# betaV2_2.net
KiCad netlist of a schematic drawn in Altium Designer
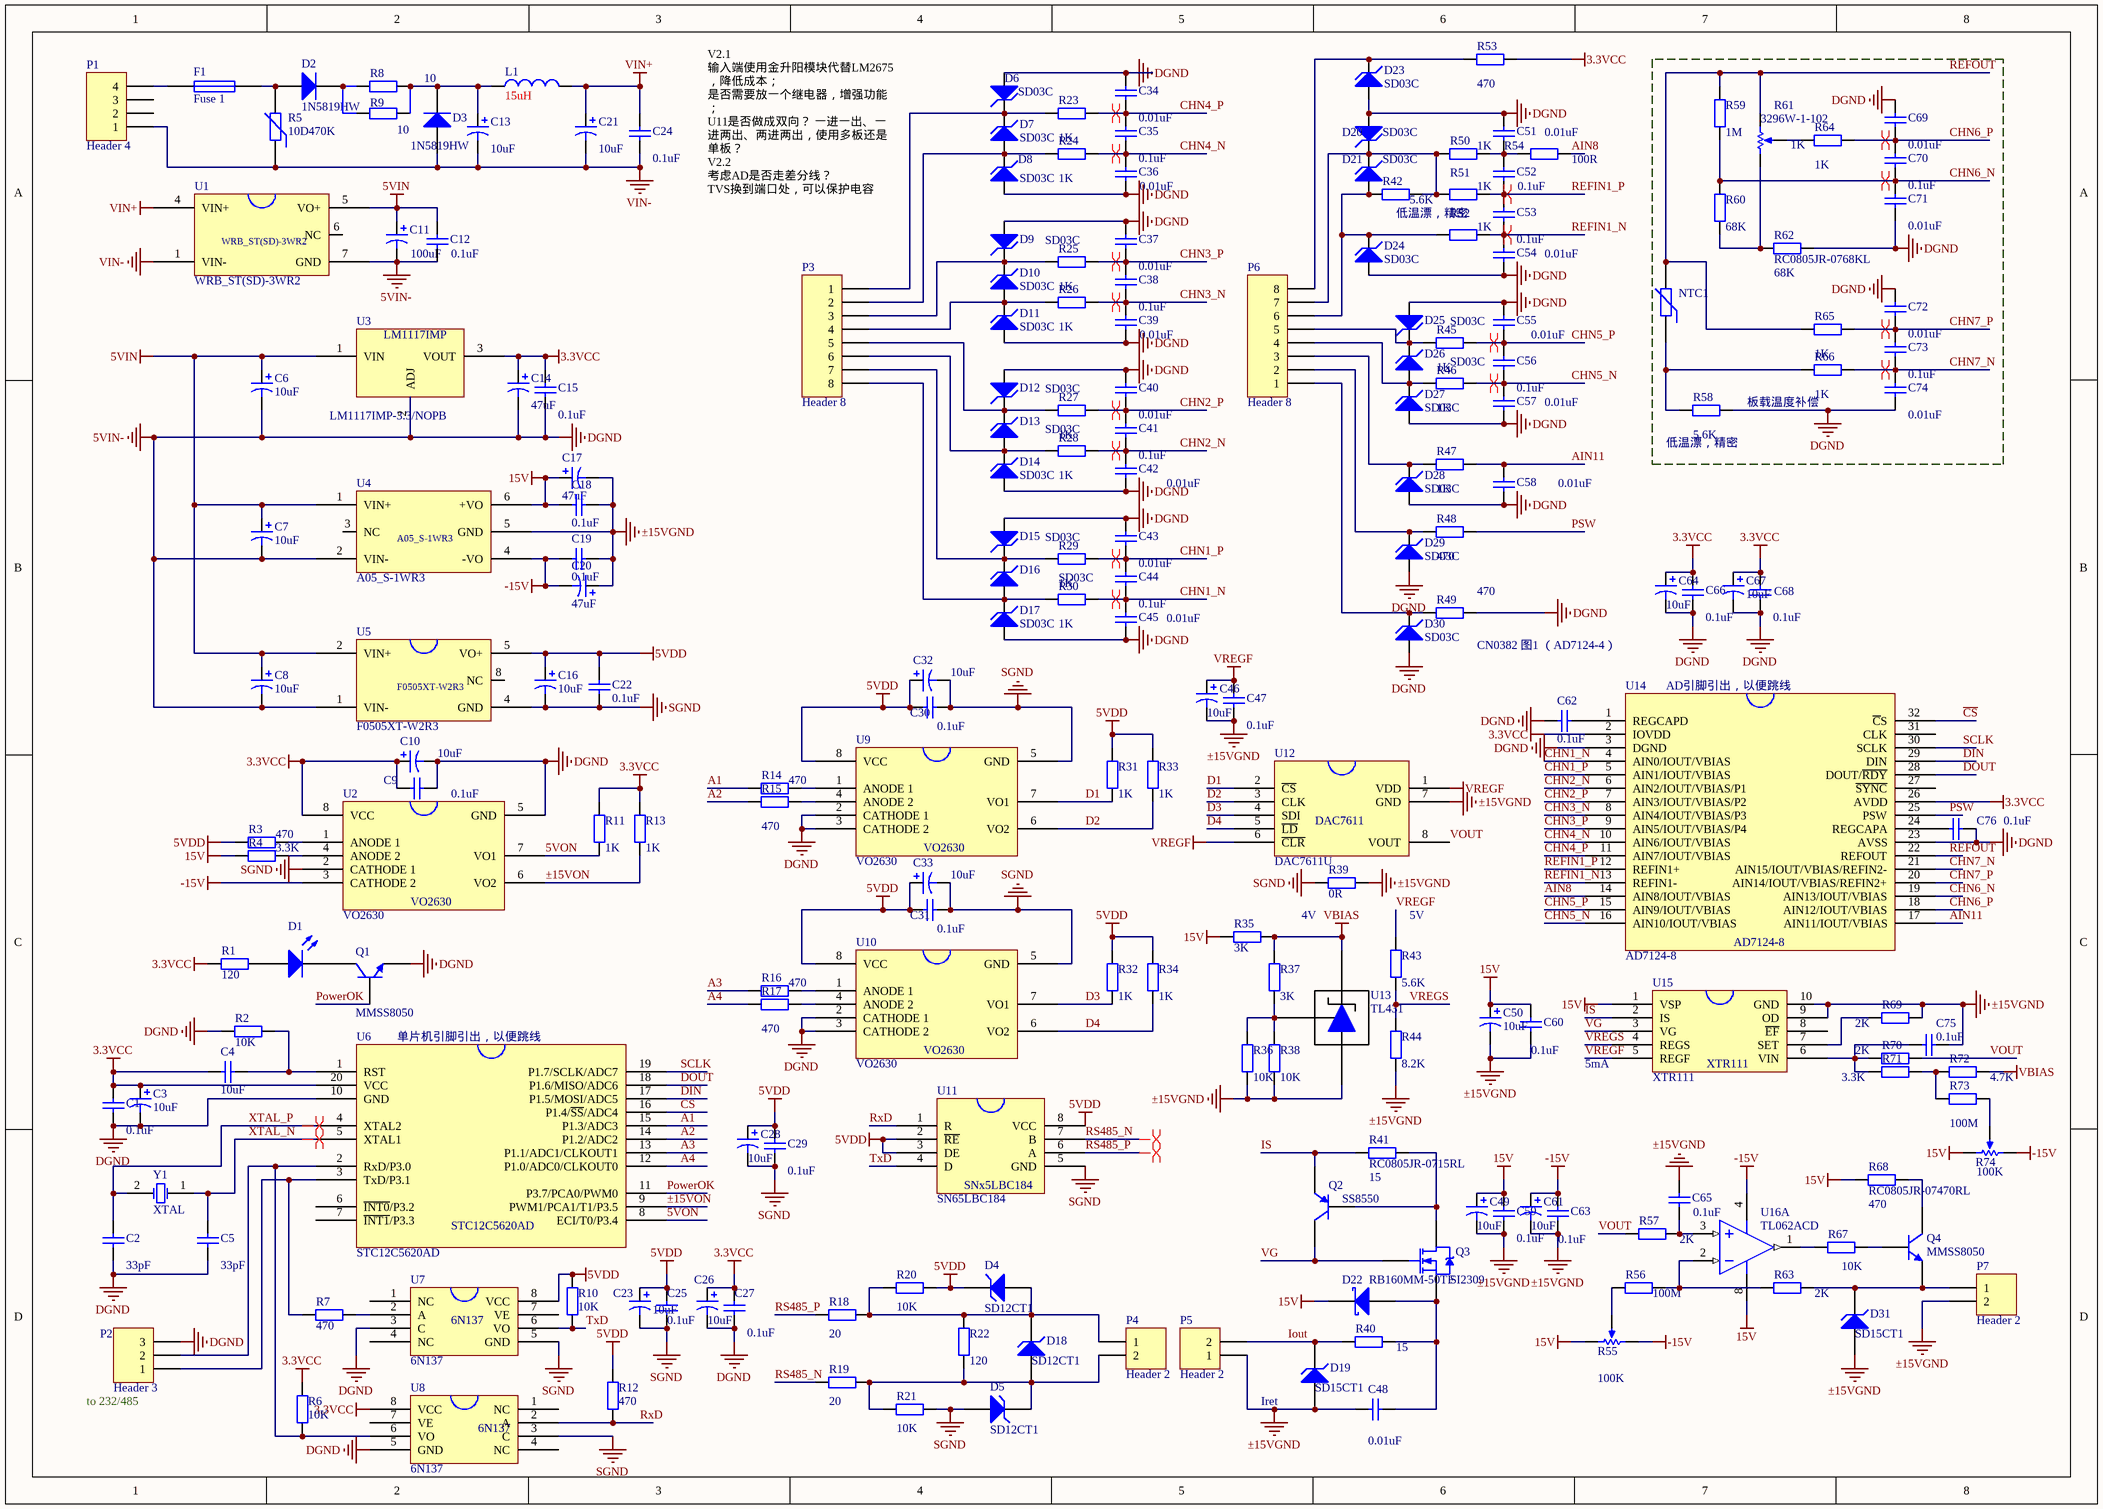
[diagram p0: betaV2.2.SchDoc]

(export (version "E")
  (design (tool "Eeschema 10.0.6"))
  (components
    (comp (ref "C1")
      (value "0.1uF")
      (footprint "0805c")
      (description "Capacitor")
      (fields (field (name "Comment") "CC0805MRX7R9BB104"))
      (libsource (lib "Miscellaneous Devices") (part "Cap"))
    )
    (comp (ref "C2")
      (value "33pF")
      (footprint "0805c")
      (description "Capacitor")
      (fields (field (name "Comment") "CC0805MRX7R9BB330") (field (name "PUBLISHER") "Altium Limited"))
      (libsource (lib "Miscellaneous Devices") (part "Cap"))
    )
    (comp (ref "C3")
      (value "10uF")
      (footprint "CB")
      (description "Polarized Capacitor (Radial)")
      (fields (field (name "Comment") "T494B106M006AHAUTO") (field (name "PUBLISHER") "Altium Limited"))
      (libsource (lib "Miscellaneous Devices") (part "Cap Pol1"))
    )
    (comp (ref "C4")
      (value "10uF")
      (footprint "0805c")
      (description "Capacitor")
      (fields (field (name "Comment") "CC0805MRX7R9BB106"))
      (libsource (lib "Miscellaneous Devices") (part "Cap"))
    )
    (comp (ref "C5")
      (value "33pF")
      (footprint "0805c")
      (description "Capacitor")
      (fields (field (name "Comment") "CC0805MRX7R9BB330") (field (name "PUBLISHER") "Altium Limited"))
      (libsource (lib "Miscellaneous Devices") (part "Cap"))
    )
    (comp (ref "C6")
      (value "10uF")
      (footprint "CB")
      (description "Polarized Capacitor (Radial)")
      (fields (field (name "Comment") "T494B106M006AHAUTO") (field (name "PUBLISHER") "Altium Limited"))
      (libsource (lib "Miscellaneous Devices") (part "Cap Pol1"))
    )
    (comp (ref "C7")
      (value "10uF")
      (footprint "CB")
      (description "Polarized Capacitor (Radial)")
      (fields (field (name "Comment") "T494B106M006AHAUTO") (field (name "PUBLISHER") "Altium Limited"))
      (libsource (lib "Miscellaneous Devices") (part "Cap Pol1"))
    )
    (comp (ref "C8")
      (value "10uF")
      (footprint "CB")
      (description "Polarized Capacitor (Radial)")
      (fields (field (name "Comment") "T494B106M006AHAUTO") (field (name "PUBLISHER") "Altium Limited"))
      (libsource (lib "Miscellaneous Devices") (part "Cap Pol1"))
    )
    (comp (ref "C9")
      (value "0.1uF")
      (footprint "0805c")
      (description "Capacitor")
      (fields (field (name "Comment") "CC0805MRX7R9BB104") (field (name "PUBLISHER") "Altium Limited"))
      (libsource (lib "Miscellaneous Devices") (part "Cap"))
    )
    (comp (ref "C10")
      (value "10uF")
      (footprint "CB")
      (description "Polarized Capacitor (Radial)")
      (fields (field (name "Comment") "T494B106M006AHAUTO") (field (name "PUBLISHER") "Altium Limited"))
      (libsource (lib "Miscellaneous Devices") (part "Cap Pol1"))
    )
    (comp (ref "C11")
      (value "100uF")
      (footprint "CB")
      (description "Polarized Capacitor (Radial)")
      (fields (field (name "Comment") "T494B107M006AHAUTO") (field (name "PUBLISHER") "Altium Limited"))
      (libsource (lib "Miscellaneous Devices") (part "Cap Pol1"))
    )
    (comp (ref "C12")
      (value "0.1uF")
      (footprint "0805c")
      (description "Capacitor")
      (fields (field (name "Comment") "CC0805MRX7R9BB104") (field (name "PUBLISHER") "Altium Limited"))
      (libsource (lib "Miscellaneous Devices") (part "Cap"))
    )
    (comp (ref "C13")
      (value "10uF")
      (footprint "Φ6.3×11.5")
      (description "Polarized Capacitor (Radial)")
      (fields (field (name "Comment") "ECR1HQG100M-063007") (field (name "PUBLISHER") "Altium Limited"))
      (libsource (lib "Miscellaneous Devices") (part "Cap Pol1"))
    )
    (comp (ref "C14")
      (value "47uF")
      (footprint "CB")
      (description "Polarized Capacitor (Radial)")
      (fields (field (name "Comment") "T494B476M010AHAUTO") (field (name "PUBLISHER") "Altium Limited"))
      (libsource (lib "Miscellaneous Devices") (part "Cap Pol1"))
    )
    (comp (ref "C15")
      (value "0.1uF")
      (footprint "0805c")
      (description "Capacitor")
      (fields (field (name "Comment") "CC0805MRX7R9BB104") (field (name "PUBLISHER") "Altium Limited"))
      (libsource (lib "Miscellaneous Devices") (part "Cap"))
    )
    (comp (ref "C16")
      (value "10uF")
      (footprint "CB")
      (description "Polarized Capacitor (Radial)")
      (fields (field (name "Comment") "T494B106M006AHAUTO") (field (name "PUBLISHER") "Altium Limited"))
      (libsource (lib "Miscellaneous Devices") (part "Cap Pol1"))
    )
    (comp (ref "C17")
      (value "47uF")
      (footprint "CB")
      (description "Polarized Capacitor (Radial)")
      (fields (field (name "Comment") "T494B476K025ATAUTO") (field (name "PUBLISHER") "Altium Limited"))
      (libsource (lib "Miscellaneous Devices") (part "Cap Pol1"))
    )
    (comp (ref "C18")
      (value "0.1uF")
      (footprint "0805c")
      (description "Capacitor")
      (fields (field (name "Comment") "CC0805MRX7R9BB104") (field (name "PUBLISHER") "Altium Limited"))
      (libsource (lib "Miscellaneous Devices") (part "Cap"))
    )
    (comp (ref "C19")
      (value "0.1uF")
      (footprint "0805c")
      (description "Capacitor")
      (fields (field (name "Comment") "CC0805MRX7R9BB104") (field (name "PUBLISHER") "Altium Limited"))
      (libsource (lib "Miscellaneous Devices") (part "Cap"))
    )
    (comp (ref "C20")
      (value "47uF")
      (footprint "CB")
      (description "Polarized Capacitor (Radial)")
      (fields (field (name "Comment") "T494B476K025ATAUTO") (field (name "PUBLISHER") "Altium Limited"))
      (libsource (lib "Miscellaneous Devices") (part "Cap Pol1"))
    )
    (comp (ref "C21")
      (value "10uF")
      (footprint "Φ6.3×11.5")
      (description "Polarized Capacitor (Radial)")
      (fields (field (name "Comment") "ECR1HQG100M-063007") (field (name "PUBLISHER") "Altium Limited"))
      (libsource (lib "Miscellaneous Devices") (part "Cap Pol1"))
    )
    (comp (ref "C22")
      (value "0.1uF")
      (footprint "0805c")
      (description "Capacitor")
      (fields (field (name "Comment") "CC0805MRX7R9BB104") (field (name "PUBLISHER") "Altium Limited"))
      (libsource (lib "Miscellaneous Devices") (part "Cap"))
    )
    (comp (ref "C23")
      (value "10uF")
      (footprint "CB")
      (description "Polarized Capacitor (Radial)")
      (fields (field (name "Comment") "T494B106M006AHAUTO") (field (name "PUBLISHER") "Altium Limited"))
      (libsource (lib "Miscellaneous Devices") (part "Cap Pol1"))
    )
    (comp (ref "C24")
      (value "0.1uF")
      (footprint "0805c")
      (description "Capacitor")
      (fields (field (name "Comment") "CC0805MRX7R9BB104") (field (name "PUBLISHER") "Altium Limited"))
      (libsource (lib "Miscellaneous Devices") (part "Cap"))
    )
    (comp (ref "C25")
      (value "0.1uF")
      (footprint "0805c")
      (description "Capacitor")
      (fields (field (name "Comment") "CC0805MRX7R9BB104") (field (name "PUBLISHER") "Altium Limited"))
      (libsource (lib "Miscellaneous Devices") (part "Cap"))
    )
    (comp (ref "C26")
      (value "10uF")
      (footprint "CB")
      (description "Polarized Capacitor (Radial)")
      (fields (field (name "Comment") "T494B106M006AHAUTO") (field (name "PUBLISHER") "Altium Limited"))
      (libsource (lib "Miscellaneous Devices") (part "Cap Pol1"))
    )
    (comp (ref "C27")
      (value "0.1uF")
      (footprint "0805c")
      (description "Capacitor")
      (fields (field (name "Comment") "CC0805MRX7R9BB104") (field (name "PUBLISHER") "Altium Limited"))
      (libsource (lib "Miscellaneous Devices") (part "Cap"))
    )
    (comp (ref "C28")
      (value "10uF")
      (footprint "CB")
      (description "Polarized Capacitor (Radial)")
      (fields (field (name "Comment") "T494B106M006AHAUTO") (field (name "PUBLISHER") "Altium Limited"))
      (libsource (lib "Miscellaneous Devices") (part "Cap Pol1"))
    )
    (comp (ref "C29")
      (value "0.1uF")
      (footprint "0805c")
      (description "Capacitor")
      (fields (field (name "Comment") "CC0805MRX7R9BB104") (field (name "PUBLISHER") "Altium Limited"))
      (libsource (lib "Miscellaneous Devices") (part "Cap"))
    )
    (comp (ref "C30")
      (value "0.1uF")
      (footprint "0805c")
      (description "Capacitor")
      (fields (field (name "Comment") "CC0805MRX7R9BB104") (field (name "PUBLISHER") "Altium Limited"))
      (libsource (lib "Miscellaneous Devices") (part "Cap"))
    )
    (comp (ref "C31")
      (value "0.1uF")
      (footprint "0805c")
      (description "Capacitor")
      (fields (field (name "Comment") "CC0805MRX7R9BB104") (field (name "PUBLISHER") "Altium Limited"))
      (libsource (lib "Miscellaneous Devices") (part "Cap"))
    )
    (comp (ref "C32")
      (value "10uF")
      (footprint "CB")
      (description "Polarized Capacitor (Radial)")
      (fields (field (name "Comment") "T494B106M006AHAUTO") (field (name "PUBLISHER") "Altium Limited"))
      (libsource (lib "Miscellaneous Devices") (part "Cap Pol1"))
    )
    (comp (ref "C33")
      (value "10uF")
      (footprint "CB")
      (description "Polarized Capacitor (Radial)")
      (fields (field (name "Comment") "T494B106M006AHAUTO") (field (name "PUBLISHER") "Altium Limited"))
      (libsource (lib "Miscellaneous Devices") (part "Cap Pol1"))
    )
    (comp (ref "C34")
      (value "0.01uF")
      (footprint "0805c")
      (description "Capacitor")
      (fields (field (name "Comment") "CC0805MRX7R9BB103") (field (name "PUBLISHER") "Altium Limited"))
      (libsource (lib "Miscellaneous Devices") (part "Cap"))
    )
    (comp (ref "C35")
      (value "0.1uF")
      (footprint "0805c")
      (description "Capacitor")
      (fields (field (name "Comment") "CC0805MRX7R9BB104") (field (name "PUBLISHER") "Altium Limited"))
      (libsource (lib "Miscellaneous Devices") (part "Cap"))
    )
    (comp (ref "C36")
      (value "0.01uF")
      (footprint "0805c")
      (description "Capacitor")
      (fields (field (name "Comment") "CC0805MRX7R9BB103") (field (name "PUBLISHER") "Altium Limited"))
      (libsource (lib "Miscellaneous Devices") (part "Cap"))
    )
    (comp (ref "C37")
      (value "0.01uF")
      (footprint "0805c")
      (description "Capacitor")
      (fields (field (name "Comment") "CC0805MRX7R9BB103") (field (name "PUBLISHER") "Altium Limited"))
      (libsource (lib "Miscellaneous Devices") (part "Cap"))
    )
    (comp (ref "C38")
      (value "0.1uF")
      (footprint "0805c")
      (description "Capacitor")
      (fields (field (name "Comment") "CC0805MRX7R9BB104") (field (name "PUBLISHER") "Altium Limited"))
      (libsource (lib "Miscellaneous Devices") (part "Cap"))
    )
    (comp (ref "C39")
      (value "0.01uF")
      (footprint "0805c")
      (description "Capacitor")
      (fields (field (name "Comment") "CC0805MRX7R9BB103") (field (name "PUBLISHER") "Altium Limited"))
      (libsource (lib "Miscellaneous Devices") (part "Cap"))
    )
    (comp (ref "C40")
      (value "0.01uF")
      (footprint "0805c")
      (description "Capacitor")
      (fields (field (name "Comment") "CC0805MRX7R9BB103") (field (name "PUBLISHER") "Altium Limited"))
      (libsource (lib "Miscellaneous Devices") (part "Cap"))
    )
    (comp (ref "C41")
      (value "0.1uF")
      (footprint "0805c")
      (description "Capacitor")
      (fields (field (name "Comment") "CC0805MRX7R9BB104") (field (name "PUBLISHER") "Altium Limited"))
      (libsource (lib "Miscellaneous Devices") (part "Cap"))
    )
    (comp (ref "C42")
      (value "0.01uF")
      (footprint "0805c")
      (description "Capacitor")
      (fields (field (name "Comment") "CC0805MRX7R9BB103") (field (name "PUBLISHER") "Altium Limited"))
      (libsource (lib "Miscellaneous Devices") (part "Cap"))
    )
    (comp (ref "C43")
      (value "0.01uF")
      (footprint "0805c")
      (description "Capacitor")
      (fields (field (name "Comment") "CC0805MRX7R9BB103") (field (name "PUBLISHER") "Altium Limited"))
      (libsource (lib "Miscellaneous Devices") (part "Cap"))
    )
    (comp (ref "C44")
      (value "0.1uF")
      (footprint "0805c")
      (description "Capacitor")
      (fields (field (name "Comment") "CC0805MRX7R9BB104") (field (name "PUBLISHER") "Altium Limited"))
      (libsource (lib "Miscellaneous Devices") (part "Cap"))
    )
    (comp (ref "C45")
      (value "0.01uF")
      (footprint "0805c")
      (description "Capacitor")
      (fields (field (name "Comment") "CC0805MRX7R9BB103") (field (name "PUBLISHER") "Altium Limited"))
      (libsource (lib "Miscellaneous Devices") (part "Cap"))
    )
    (comp (ref "C46")
      (value "10uF")
      (footprint "CB")
      (description "Polarized Capacitor (Radial)")
      (fields (field (name "Comment") "T494B106M006AHAUTO") (field (name "PUBLISHER") "Altium Limited"))
      (libsource (lib "Miscellaneous Devices") (part "Cap Pol1"))
    )
    (comp (ref "C47")
      (value "0.1uF")
      (footprint "0805c")
      (description "Capacitor")
      (fields (field (name "Comment") "CC0805MRX7R9BB104") (field (name "PUBLISHER") "Altium Limited"))
      (libsource (lib "Miscellaneous Devices") (part "Cap"))
    )
    (comp (ref "C48")
      (value "0.01uF")
      (footprint "0805c")
      (description "Capacitor")
      (fields (field (name "Comment") "CC0805MRX7R9BB103") (field (name "PUBLISHER") "Altium Limited"))
      (libsource (lib "Miscellaneous Devices") (part "Cap"))
    )
    (comp (ref "C49")
      (value "10uF")
      (footprint "CB")
      (description "Polarized Capacitor (Radial)")
      (fields (field (name "Comment") "T494B106M025AHAUTO") (field (name "PUBLISHER") "Altium Limited"))
      (libsource (lib "Miscellaneous Devices") (part "Cap Pol1"))
    )
    (comp (ref "C50")
      (value "10uF")
      (footprint "CB")
      (description "Polarized Capacitor (Radial)")
      (fields (field (name "Comment") "T494B106M025AHAUTO") (field (name "PUBLISHER") "Altium Limited"))
      (libsource (lib "Miscellaneous Devices") (part "Cap Pol1"))
    )
    (comp (ref "C51")
      (value "0.01uF")
      (footprint "0805c")
      (description "Capacitor")
      (fields (field (name "Comment") "CC0805MRX7R9BB103") (field (name "PUBLISHER") "Altium Limited"))
      (libsource (lib "Miscellaneous Devices") (part "Cap"))
    )
    (comp (ref "C52")
      (value "0.1uF")
      (footprint "0805c")
      (description "Capacitor")
      (fields (field (name "Comment") "CC0805MRX7R9BB104") (field (name "PUBLISHER") "Altium Limited"))
      (libsource (lib "Miscellaneous Devices") (part "Cap"))
    )
    (comp (ref "C53")
      (value "0.1uF")
      (footprint "0805c")
      (description "Capacitor")
      (fields (field (name "Comment") "CC0805MRX7R9BB104") (field (name "PUBLISHER") "Altium Limited"))
      (libsource (lib "Miscellaneous Devices") (part "Cap"))
    )
    (comp (ref "C54")
      (value "0.01uF")
      (footprint "0805c")
      (description "Capacitor")
      (fields (field (name "Comment") "CC0805MRX7R9BB103") (field (name "PUBLISHER") "Altium Limited"))
      (libsource (lib "Miscellaneous Devices") (part "Cap"))
    )
    (comp (ref "C55")
      (value "0.01uF")
      (footprint "0805c")
      (description "Capacitor")
      (fields (field (name "Comment") "CC0805MRX7R9BB103") (field (name "PUBLISHER") "Altium Limited"))
      (libsource (lib "Miscellaneous Devices") (part "Cap"))
    )
    (comp (ref "C56")
      (value "0.1uF")
      (footprint "0805c")
      (description "Capacitor")
      (fields (field (name "Comment") "CC0805MRX7R9BB104") (field (name "PUBLISHER") "Altium Limited"))
      (libsource (lib "Miscellaneous Devices") (part "Cap"))
    )
    (comp (ref "C57")
      (value "0.01uF")
      (footprint "0805c")
      (description "Capacitor")
      (fields (field (name "Comment") "CC0805MRX7R9BB103") (field (name "PUBLISHER") "Altium Limited"))
      (libsource (lib "Miscellaneous Devices") (part "Cap"))
    )
    (comp (ref "C58")
      (value "0.01uF")
      (footprint "0805c")
      (description "Capacitor")
      (fields (field (name "Comment") "CC0805MRX7R9BB103") (field (name "PUBLISHER") "Altium Limited"))
      (libsource (lib "Miscellaneous Devices") (part "Cap"))
    )
    (comp (ref "C59")
      (value "0.1uF")
      (footprint "0805c")
      (description "Capacitor")
      (fields (field (name "Comment") "CC0805MRX7R9BB104") (field (name "PUBLISHER") "Altium Limited"))
      (libsource (lib "Miscellaneous Devices") (part "Cap"))
    )
    (comp (ref "C60")
      (value "0.1uF")
      (footprint "0805c")
      (description "Capacitor")
      (fields (field (name "Comment") "CC0805MRX7R9BB104") (field (name "PUBLISHER") "Altium Limited"))
      (libsource (lib "Miscellaneous Devices") (part "Cap"))
    )
    (comp (ref "C61")
      (value "10uF")
      (footprint "CB")
      (description "Polarized Capacitor (Radial)")
      (fields (field (name "Comment") "T494B106M025AHAUTO") (field (name "PUBLISHER") "Altium Limited"))
      (libsource (lib "Miscellaneous Devices") (part "Cap Pol1"))
    )
    (comp (ref "C62")
      (value "0.1uF")
      (footprint "0805c")
      (description "Capacitor")
      (fields (field (name "Comment") "CC0805MRX7R9BB104") (field (name "PUBLISHER") "Altium Limited"))
      (libsource (lib "Miscellaneous Devices") (part "Cap"))
    )
    (comp (ref "C63")
      (value "0.1uF")
      (footprint "0805c")
      (description "Capacitor")
      (fields (field (name "Comment") "CC0805MRX7R9BB104") (field (name "PUBLISHER") "Altium Limited"))
      (libsource (lib "Miscellaneous Devices") (part "Cap"))
    )
    (comp (ref "C64")
      (value "10uF")
      (footprint "CB")
      (description "Polarized Capacitor (Radial)")
      (fields (field (name "Comment") "T494B106M006AHAUTO") (field (name "PUBLISHER") "Altium Limited"))
      (libsource (lib "Miscellaneous Devices") (part "Cap Pol1"))
    )
    (comp (ref "C65")
      (value "0.1uF")
      (footprint "0805c")
      (description "Capacitor")
      (fields (field (name "Comment") "CC0805MRX7R9BB104") (field (name "PUBLISHER") "Altium Limited"))
      (libsource (lib "Miscellaneous Devices") (part "Cap"))
    )
    (comp (ref "C66")
      (value "0.1uF")
      (footprint "0805c")
      (description "Capacitor")
      (fields (field (name "Comment") "CC0805MRX7R9BB104") (field (name "PUBLISHER") "Altium Limited"))
      (libsource (lib "Miscellaneous Devices") (part "Cap"))
    )
    (comp (ref "C67")
      (value "10uF")
      (footprint "CB")
      (description "Polarized Capacitor (Radial)")
      (fields (field (name "Comment") "T494B106M006AHAUTO") (field (name "PUBLISHER") "Altium Limited"))
      (libsource (lib "Miscellaneous Devices") (part "Cap Pol1"))
    )
    (comp (ref "C68")
      (value "0.1uF")
      (footprint "0805c")
      (description "Capacitor")
      (fields (field (name "Comment") "CC0805MRX7R9BB104") (field (name "PUBLISHER") "Altium Limited"))
      (libsource (lib "Miscellaneous Devices") (part "Cap"))
    )
    (comp (ref "C69")
      (value "0.01uF")
      (footprint "0805c")
      (description "Capacitor")
      (fields (field (name "Comment") "CC0805MRX7R9BB103") (field (name "PUBLISHER") "Altium Limited"))
      (libsource (lib "Miscellaneous Devices") (part "Cap"))
    )
    (comp (ref "C70")
      (value "0.1uF")
      (footprint "0805c")
      (description "Capacitor")
      (fields (field (name "Comment") "CC0805MRX7R9BB104") (field (name "PUBLISHER") "Altium Limited"))
      (libsource (lib "Miscellaneous Devices") (part "Cap"))
    )
    (comp (ref "C71")
      (value "0.01uF")
      (footprint "0805c")
      (description "Capacitor")
      (fields (field (name "Comment") "CC0805MRX7R9BB103") (field (name "PUBLISHER") "Altium Limited"))
      (libsource (lib "Miscellaneous Devices") (part "Cap"))
    )
    (comp (ref "C72")
      (value "0.01uF")
      (footprint "0805c")
      (description "Capacitor")
      (fields (field (name "Comment") "CC0805MRX7R9BB103") (field (name "PUBLISHER") "Altium Limited"))
      (libsource (lib "Miscellaneous Devices") (part "Cap"))
    )
    (comp (ref "C73")
      (value "0.1uF")
      (footprint "0805c")
      (description "Capacitor")
      (fields (field (name "Comment") "CC0805MRX7R9BB104") (field (name "PUBLISHER") "Altium Limited"))
      (libsource (lib "Miscellaneous Devices") (part "Cap"))
    )
    (comp (ref "C74")
      (value "0.01uF")
      (footprint "0805c")
      (description "Capacitor")
      (fields (field (name "Comment") "CC0805MRX7R9BB103") (field (name "PUBLISHER") "Altium Limited"))
      (libsource (lib "Miscellaneous Devices") (part "Cap"))
    )
    (comp (ref "C75")
      (value "0.1uF")
      (footprint "0805c")
      (description "Capacitor")
      (fields (field (name "Comment") "CC0805MRX7R9BB104") (field (name "PUBLISHER") "Altium Limited"))
      (libsource (lib "Miscellaneous Devices") (part "Cap"))
    )
    (comp (ref "C76")
      (value "0.1uF")
      (footprint "0805c")
      (description "Capacitor")
      (fields (field (name "Comment") "CC0805MRX7R9BB104") (field (name "PUBLISHER") "Altium Limited"))
      (libsource (lib "Miscellaneous Devices") (part "Cap"))
    )
    (comp (ref "D1")
      (value "150080GS75000")
      (footprint "LEDΦ3.0")
      (description "Typical RED, GREEN, YELLOW, AMBER GaAs LED")
      (fields (field (name "PUBLISHER") "Altium Limited"))
      (libsource (lib "Miscellaneous Devices") (part "LED2"))
    )
    (comp (ref "D2")
      (value "1N5819HW")
      (footprint "sod123")
      (description "Default Diode")
      (fields (field (name "PUBLISHER") "Altium Limited"))
      (libsource (lib "Miscellaneous Devices") (part "Diode"))
    )
    (comp (ref "D3")
      (value "1N5819HW")
      (footprint "sod123")
      (description "Default Diode")
      (fields (field (name "PUBLISHER") "Altium Limited"))
      (libsource (lib "Miscellaneous Devices") (part "Diode"))
    )
    (comp (ref "D4")
      (value "SD12CT1")
      (footprint "sod323")
      (description "Zener Diode")
      (fields (field (name "PUBLISHER") "Altium Limited"))
      (libsource (lib "Miscellaneous Devices") (part "D Zener"))
    )
    (comp (ref "D5")
      (value "SD12CT1")
      (footprint "sod323")
      (description "Zener Diode")
      (fields (field (name "PUBLISHER") "Altium Limited"))
      (libsource (lib "Miscellaneous Devices") (part "D Zener"))
    )
    (comp (ref "D6")
      (value "SD03C")
      (footprint "sod323")
      (libsource (lib "Standard-V0.0") (part "TVS DIODE"))
    )
    (comp (ref "D7")
      (value "SD03C")
      (footprint "sod323")
      (libsource (lib "Standard-V0.0") (part "TVS DIODE"))
    )
    (comp (ref "D8")
      (value "SD03C")
      (footprint "sod323")
      (libsource (lib "Standard-V0.0") (part "TVS DIODE"))
    )
    (comp (ref "D9")
      (value "SD03C")
      (footprint "sod323")
      (libsource (lib "Standard-V0.0") (part "TVS DIODE"))
    )
    (comp (ref "D10")
      (value "SD03C")
      (footprint "sod323")
      (libsource (lib "Standard-V0.0") (part "TVS DIODE"))
    )
    (comp (ref "D11")
      (value "SD03C")
      (footprint "sod323")
      (libsource (lib "Standard-V0.0") (part "TVS DIODE"))
    )
    (comp (ref "D12")
      (value "SD03C")
      (footprint "sod323")
      (libsource (lib "Standard-V0.0") (part "TVS DIODE"))
    )
    (comp (ref "D13")
      (value "SD03C")
      (footprint "sod323")
      (libsource (lib "Standard-V0.0") (part "TVS DIODE"))
    )
    (comp (ref "D14")
      (value "SD03C")
      (footprint "sod323")
      (libsource (lib "Standard-V0.0") (part "TVS DIODE"))
    )
    (comp (ref "D15")
      (value "SD03C")
      (footprint "sod323")
      (libsource (lib "Standard-V0.0") (part "TVS DIODE"))
    )
    (comp (ref "D16")
      (value "SD03C")
      (footprint "sod323")
      (libsource (lib "Standard-V0.0") (part "TVS DIODE"))
    )
    (comp (ref "D17")
      (value "SD03C")
      (footprint "sod323")
      (libsource (lib "Standard-V0.0") (part "TVS DIODE"))
    )
    (comp (ref "D18")
      (value "SD12CT1")
      (footprint "sod323")
      (description "Zener Diode")
      (fields (field (name "PUBLISHER") "Altium Limited"))
      (libsource (lib "Miscellaneous Devices") (part "D Zener"))
    )
    (comp (ref "D19")
      (value "SD15CT1")
      (footprint "sod323")
      (description "Zener Diode")
      (fields (field (name "PUBLISHER") "Altium Limited"))
      (libsource (lib "Miscellaneous Devices") (part "D Zener"))
    )
    (comp (ref "D20")
      (value "SD03C")
      (footprint "sod323")
      (libsource (lib "Standard-V0.0") (part "TVS DIODE"))
    )
    (comp (ref "D21")
      (value "SD03C")
      (footprint "sod323")
      (libsource (lib "Standard-V0.0") (part "TVS DIODE"))
    )
    (comp (ref "D22")
      (value "RB160MM-50TF")
      (footprint "sod123")
      (description "Schottky Diode")
      (fields (field (name "PUBLISHER") "Altium Limited"))
      (libsource (lib "Miscellaneous Devices") (part "D Schottky"))
    )
    (comp (ref "D23")
      (value "SD03C")
      (footprint "sod323")
      (libsource (lib "Standard-V0.0") (part "TVS DIODE"))
    )
    (comp (ref "D24")
      (value "SD03C")
      (footprint "sod323")
      (libsource (lib "Standard-V0.0") (part "TVS DIODE"))
    )
    (comp (ref "D25")
      (value "SD03C")
      (footprint "sod323")
      (libsource (lib "Standard-V0.0") (part "TVS DIODE"))
    )
    (comp (ref "D26")
      (value "SD03C")
      (footprint "sod323")
      (libsource (lib "Standard-V0.0") (part "TVS DIODE"))
    )
    (comp (ref "D27")
      (value "SD03C")
      (footprint "sod323")
      (libsource (lib "Standard-V0.0") (part "TVS DIODE"))
    )
    (comp (ref "D28")
      (value "SD03C")
      (footprint "sod323")
      (libsource (lib "Standard-V0.0") (part "TVS DIODE"))
    )
    (comp (ref "D29")
      (value "SD03C")
      (footprint "sod323")
      (libsource (lib "Standard-V0.0") (part "TVS DIODE"))
    )
    (comp (ref "D30")
      (value "SD03C")
      (footprint "sod323")
      (libsource (lib "Standard-V0.0") (part "TVS DIODE"))
    )
    (comp (ref "D31")
      (value "SD15CT1")
      (footprint "sod323")
      (description "Zener Diode")
      (fields (field (name "PUBLISHER") "Altium Limited"))
      (libsource (lib "Miscellaneous Devices") (part "D Zener"))
    )
    (comp (ref "F1")
      (value "Fuse 1")
      (footprint "0805r")
      (description "Fuse")
      (fields (field (name "PUBLISHER") "Altium Limited"))
      (libsource (lib "Miscellaneous Devices") (part "Fuse 1"))
    )
    (comp (ref "L1")
      (value "15uH")
      (footprint "vls4012")
      (fields (field (name "Comment") "VLS4012HBX-150M"))
      (libsource (lib "Miscellaneous Devices") (part "Inductor"))
    )
    (comp (ref "NTC1")
      (value "NTCS0805E3103JHT")
      (footprint "0805r")
      (description "Varistor (Voltage-Sensitive Resistor)")
      (fields (field (name "PUBLISHER") "Altium Limited"))
      (libsource (lib "Miscellaneous Devices") (part "Res Varistor"))
    )
    (comp (ref "P1")
      (value "Header 4")
      (footprint "HDR1X4")
      (description "Header, 4-Pin")
      (fields (field (name "PUBLISHER") "Altium Limited"))
      (libsource (lib "Miscellaneous Connectors") (part "Header 4"))
    )
    (comp (ref "P2")
      (value "Header 3")
      (footprint "HDR1X3")
      (description "Header, 3-Pin")
      (fields (field (name "PUBLISHER") "Altium Limited"))
      (libsource (lib "Miscellaneous Connectors") (part "Header 3"))
    )
    (comp (ref "P3")
      (value "Header 8")
      (footprint "HDR1X8")
      (description "Header, 8-Pin")
      (fields (field (name "PUBLISHER") "Altium Limited"))
      (libsource (lib "") (part "Header 8_1"))
    )
    (comp (ref "P4")
      (value "Header 2")
      (footprint "HDR1X2")
      (description "Header, 2-Pin")
      (fields (field (name "PUBLISHER") "Altium Limited"))
      (libsource (lib "") (part "Header 2_1"))
    )
    (comp (ref "P5")
      (value "Header 2")
      (footprint "HDR1X2")
      (description "Header, 2-Pin")
      (fields (field (name "PUBLISHER") "Altium Limited"))
      (libsource (lib "Miscellaneous Connectors") (part "Header 2"))
    )
    (comp (ref "P6")
      (value "Header 8")
      (footprint "HDR1X8")
      (description "Header, 8-Pin")
      (fields (field (name "PUBLISHER") "Altium Limited"))
      (libsource (lib "Miscellaneous Connectors") (part "Header 8"))
    )
    (comp (ref "P7")
      (value "Header 2")
      (footprint "HDR1X2")
      (description "Header, 2-Pin")
      (fields (field (name "PUBLISHER") "Altium Limited"))
      (libsource (lib "") (part "Header 2_1"))
    )
    (comp (ref "Q1")
      (value "MMSS8050")
      (footprint "SOT-23-BJT")
      (description "NPN Bipolar Transistor")
      (fields (field (name "PUBLISHER") "Altium Limited"))
      (libsource (lib "Miscellaneous Devices") (part "NPN"))
    )
    (comp (ref "Q2")
      (value "SS8550")
      (footprint "SOT-23-BJT")
      (description "PNP Bipolar Transistor")
      (fields (field (name "PUBLISHER") "Altium Limited"))
      (libsource (lib "Miscellaneous Devices") (part "PNP"))
    )
    (comp (ref "Q3")
      (value "SI2309")
      (footprint "SOT-23-MOS")
      (description "N-Channel Power MOSFET")
      (fields (field (name "PUBLISHER") "Altium Limited"))
      (libsource (lib "Miscellaneous Devices") (part "NMOS-2"))
    )
    (comp (ref "Q4")
      (value "MMSS8050")
      (footprint "SOT-23-BJT")
      (description "NPN Bipolar Transistor")
      (fields (field (name "PUBLISHER") "Altium Limited"))
      (libsource (lib "Miscellaneous Devices") (part "NPN"))
    )
    (comp (ref "R1")
      (value "120")
      (footprint "0805R")
      (description "Resistor")
      (fields (field (name "Comment") "RC0805JR-07120RL") (field (name "PUBLISHER") "Altium Limited"))
      (libsource (lib "Miscellaneous Devices") (part "Res2"))
    )
    (comp (ref "R2")
      (value "10K")
      (footprint "0805R")
      (description "Resistor")
      (fields (field (name "Comment") "RC0805JR-0710KL") (field (name "PUBLISHER") "Altium Limited"))
      (libsource (lib "Miscellaneous Devices") (part "Res2"))
    )
    (comp (ref "R3")
      (value "470")
      (footprint "0805R")
      (description "Resistor")
      (fields (field (name "Comment") "RC0805JR-07470RL") (field (name "PUBLISHER") "Altium Limited"))
      (libsource (lib "") (part "Res2_2"))
    )
    (comp (ref "R4")
      (value "3.3K")
      (footprint "0805R")
      (description "Resistor")
      (fields (field (name "Comment") "RC0805JR-073300RL") (field (name "PUBLISHER") "Altium Limited"))
      (libsource (lib "") (part "Res2_2"))
    )
    (comp (ref "R5")
      (value "10D470K")
      (footprint "mov")
      (description "Varistor (Voltage-Sensitive Resistor)")
      (fields (field (name "PUBLISHER") "Altium Limited"))
      (libsource (lib "Miscellaneous Devices") (part "Res Varistor"))
    )
    (comp (ref "R6")
      (value "10K")
      (footprint "0805R")
      (description "Resistor")
      (fields (field (name "Comment") "RC0805JR-0710KRL") (field (name "PUBLISHER") "Altium Limited"))
      (libsource (lib "") (part "Res2_3"))
    )
    (comp (ref "R7")
      (value "470")
      (footprint "0805R")
      (description "Resistor")
      (fields (field (name "Comment") "RC0805JR-07470RL") (field (name "PUBLISHER") "Altium Limited"))
      (libsource (lib "Miscellaneous Devices") (part "Res2"))
    )
    (comp (ref "R8")
      (value "10")
      (footprint "0805R")
      (description "Resistor")
      (fields (field (name "Comment") "PNP-200KJBJ26-10R") (field (name "PUBLISHER") "Altium Limited"))
      (libsource (lib "") (part "Res2_2"))
    )
    (comp (ref "R9")
      (value "10")
      (footprint "0805R")
      (description "Resistor")
      (fields (field (name "Comment") "PNP-200KJBJ26-10R") (field (name "PUBLISHER") "Altium Limited"))
      (libsource (lib "") (part "Res2_2"))
    )
    (comp (ref "R10")
      (value "10K")
      (footprint "0805R")
      (description "Resistor")
      (fields (field (name "Comment") "RC0805JR-0710KRL") (field (name "PUBLISHER") "Altium Limited"))
      (libsource (lib "") (part "Res2_3"))
    )
    (comp (ref "R11")
      (value "1K")
      (footprint "0805R")
      (description "Resistor")
      (fields (field (name "Comment") "RC0805JR-071KL") (field (name "PUBLISHER") "Altium Limited"))
      (libsource (lib "") (part "Res2_1"))
    )
    (comp (ref "R12")
      (value "470")
      (footprint "0805R")
      (description "Resistor")
      (fields (field (name "Comment") "RC0805JR-07470RL") (field (name "PUBLISHER") "Altium Limited"))
      (libsource (lib "") (part "Res2_3"))
    )
    (comp (ref "R13")
      (value "1K")
      (footprint "0805R")
      (description "Resistor")
      (fields (field (name "Comment") "RC0805JR-071KL") (field (name "PUBLISHER") "Altium Limited"))
      (libsource (lib "") (part "Res2_1"))
    )
    (comp (ref "R14")
      (value "470")
      (footprint "0805R")
      (description "Resistor")
      (fields (field (name "Comment") "RC0805JR-07470RL") (field (name "PUBLISHER") "Altium Limited"))
      (libsource (lib "") (part "Res2_2"))
    )
    (comp (ref "R15")
      (value "470")
      (footprint "0805R")
      (description "Resistor")
      (fields (field (name "Comment") "RC0805JR-07470RL") (field (name "PUBLISHER") "Altium Limited"))
      (libsource (lib "") (part "Res2_2"))
    )
    (comp (ref "R16")
      (value "470")
      (footprint "0805R")
      (description "Resistor")
      (fields (field (name "Comment") "RC0805JR-07470RL") (field (name "PUBLISHER") "Altium Limited"))
      (libsource (lib "") (part "Res2_2"))
    )
    (comp (ref "R17")
      (value "470")
      (footprint "0805R")
      (description "Resistor")
      (fields (field (name "Comment") "RC0805JR-07470RL") (field (name "PUBLISHER") "Altium Limited"))
      (libsource (lib "") (part "Res2_2"))
    )
    (comp (ref "R18")
      (value "20")
      (footprint "0805R")
      (description "Resistor")
      (fields (field (name "Comment") "RC0805JR-0720RL") (field (name "PUBLISHER") "Altium Limited"))
      (libsource (lib "Miscellaneous Devices") (part "Res2"))
    )
    (comp (ref "R19")
      (value "20")
      (footprint "0805R")
      (description "Resistor")
      (fields (field (name "Comment") "RC0805JR-0720RL") (field (name "PUBLISHER") "Altium Limited"))
      (libsource (lib "") (part "Res2_2"))
    )
    (comp (ref "R20")
      (value "10K")
      (footprint "0805R")
      (description "Resistor")
      (fields (field (name "Comment") "RC0805JR-0710KL") (field (name "PUBLISHER") "Altium Limited"))
      (libsource (lib "") (part "Res2_2"))
    )
    (comp (ref "R21")
      (value "10K")
      (footprint "0805R")
      (description "Resistor")
      (fields (field (name "Comment") "RC0805JR-0710KL") (field (name "PUBLISHER") "Altium Limited"))
      (libsource (lib "") (part "Res2_2"))
    )
    (comp (ref "R22")
      (value "120")
      (footprint "0805R")
      (description "Resistor")
      (fields (field (name "Comment") "RC0805JR-07120RL") (field (name "PUBLISHER") "Altium Limited"))
      (libsource (lib "") (part "Res2_3"))
    )
    (comp (ref "R23")
      (value "1K")
      (footprint "0805R")
      (description "Resistor")
      (fields (field (name "Comment") "RC0805JR-071KL") (field (name "PUBLISHER") "Altium Limited"))
      (libsource (lib "") (part "Res2_2"))
    )
    (comp (ref "R24")
      (value "1K")
      (footprint "0805R")
      (description "Resistor")
      (fields (field (name "Comment") "RC0805JR-071KL") (field (name "PUBLISHER") "Altium Limited"))
      (libsource (lib "") (part "Res2_2"))
    )
    (comp (ref "R25")
      (value "1K")
      (footprint "0805R")
      (description "Resistor")
      (fields (field (name "Comment") "RC0805JR-071KL") (field (name "PUBLISHER") "Altium Limited"))
      (libsource (lib "") (part "Res2_2"))
    )
    (comp (ref "R26")
      (value "1K")
      (footprint "0805R")
      (description "Resistor")
      (fields (field (name "Comment") "RC0805JR-071KL") (field (name "PUBLISHER") "Altium Limited"))
      (libsource (lib "") (part "Res2_2"))
    )
    (comp (ref "R27")
      (value "1K")
      (footprint "0805R")
      (description "Resistor")
      (fields (field (name "Comment") "RC0805JR-071KL") (field (name "PUBLISHER") "Altium Limited"))
      (libsource (lib "") (part "Res2_2"))
    )
    (comp (ref "R28")
      (value "1K")
      (footprint "0805R")
      (description "Resistor")
      (fields (field (name "Comment") "RC0805JR-071KL") (field (name "PUBLISHER") "Altium Limited"))
      (libsource (lib "") (part "Res2_2"))
    )
    (comp (ref "R29")
      (value "1K")
      (footprint "0805R")
      (description "Resistor")
      (fields (field (name "Comment") "RC0805JR-071KL") (field (name "PUBLISHER") "Altium Limited"))
      (libsource (lib "") (part "Res2_2"))
    )
    (comp (ref "R30")
      (value "1K")
      (footprint "0805R")
      (description "Resistor")
      (fields (field (name "Comment") "RC0805JR-071KL") (field (name "PUBLISHER") "Altium Limited"))
      (libsource (lib "") (part "Res2_2"))
    )
    (comp (ref "R31")
      (value "1K")
      (footprint "0805R")
      (description "Resistor")
      (fields (field (name "Comment") "RC0805JR-071KL") (field (name "PUBLISHER") "Altium Limited"))
      (libsource (lib "") (part "Res2_1"))
    )
    (comp (ref "R32")
      (value "1K")
      (footprint "0805R")
      (description "Resistor")
      (fields (field (name "Comment") "RC0805JR-071KL") (field (name "PUBLISHER") "Altium Limited"))
      (libsource (lib "") (part "Res2_1"))
    )
    (comp (ref "R33")
      (value "1K")
      (footprint "0805R")
      (description "Resistor")
      (fields (field (name "Comment") "RC0805JR-071KL") (field (name "PUBLISHER") "Altium Limited"))
      (libsource (lib "") (part "Res2_1"))
    )
    (comp (ref "R34")
      (value "1K")
      (footprint "0805R")
      (description "Resistor")
      (fields (field (name "Comment") "RC0805JR-071KL") (field (name "PUBLISHER") "Altium Limited"))
      (libsource (lib "") (part "Res2_1"))
    )
    (comp (ref "R35")
      (value "3K")
      (footprint "0805R")
      (description "Resistor")
      (fields (field (name "Comment") "RC0805JR-073KL") (field (name "PUBLISHER") "Altium Limited"))
      (libsource (lib "Miscellaneous Devices") (part "Res2"))
    )
    (comp (ref "R36")
      (value "10K")
      (footprint "0805R")
      (description "Resistor")
      (fields (field (name "Comment") "RC0805JR-0710KL") (field (name "PUBLISHER") "Altium Limited"))
      (libsource (lib "") (part "Res2_1"))
    )
    (comp (ref "R37")
      (value "3K")
      (footprint "0805R")
      (description "Resistor")
      (fields (field (name "Comment") "RC0805JR-073KL") (field (name "PUBLISHER") "Altium Limited"))
      (libsource (lib "") (part "Res2_1"))
    )
    (comp (ref "R38")
      (value "10K")
      (footprint "0805R")
      (description "Resistor")
      (fields (field (name "Comment") "RC0805JR-0710KL") (field (name "PUBLISHER") "Altium Limited"))
      (libsource (lib "") (part "Res2_1"))
    )
    (comp (ref "R39")
      (value "0R")
      (footprint "0805R")
      (description "Resistor")
      (fields (field (name "Comment") "RC0805JR-000KL") (field (name "PUBLISHER") "Altium Limited"))
      (libsource (lib "Miscellaneous Devices") (part "Res2"))
    )
    (comp (ref "R40")
      (value "15")
      (footprint "0805R")
      (description "Resistor")
      (fields (field (name "Comment") "RC0805JR-0715RL") (field (name "PUBLISHER") "Altium Limited"))
      (libsource (lib "Miscellaneous Devices") (part "Res2"))
    )
    (comp (ref "R41")
      (value "RC0805JR-0715RL")
      (footprint "0805R")
      (description "Resistor")
      (fields (field (name "ALTIUM_VALUE") "15") (field (name "PUBLISHER") "Altium Limited"))
      (libsource (lib "") (part "Res2_2"))
    )
    (comp (ref "R42")
      (value "5.6K")
      (footprint "0805R")
      (description "Resistor")
      (fields (field (name "Comment") "RC0805JR-075600RL") (field (name "PUBLISHER") "Altium Limited"))
      (libsource (lib "Miscellaneous Devices") (part "Res2"))
    )
    (comp (ref "R43")
      (value "5.6K")
      (footprint "0805R")
      (description "Resistor")
      (fields (field (name "Comment") "RC0805JR-075600RL") (field (name "PUBLISHER") "Altium Limited"))
      (libsource (lib "") (part "Res2_1"))
    )
    (comp (ref "R44")
      (value "8.2K")
      (footprint "0805R")
      (description "Resistor")
      (fields (field (name "Comment") "RC0805JR-078200RL") (field (name "PUBLISHER") "Altium Limited"))
      (libsource (lib "") (part "Res2_1"))
    )
    (comp (ref "R45")
      (value "1K")
      (footprint "0805R")
      (description "Resistor")
      (fields (field (name "Comment") "RC0805JR-071KL") (field (name "PUBLISHER") "Altium Limited"))
      (libsource (lib "") (part "Res2_2"))
    )
    (comp (ref "R46")
      (value "1K")
      (footprint "0805R")
      (description "Resistor")
      (fields (field (name "Comment") "RC0805JR-071KL") (field (name "PUBLISHER") "Altium Limited"))
      (libsource (lib "") (part "Res2_2"))
    )
    (comp (ref "R47")
      (value "1K")
      (footprint "0805R")
      (description "Resistor")
      (fields (field (name "Comment") "RC0805JR-071KL") (field (name "PUBLISHER") "Altium Limited"))
      (libsource (lib "") (part "Res2_2"))
    )
    (comp (ref "R48")
      (value "470")
      (footprint "0805R")
      (description "Resistor")
      (fields (field (name "Comment") "RC0805JR-07470RL") (field (name "PUBLISHER") "Altium Limited"))
      (libsource (lib "") (part "Res2_2"))
    )
    (comp (ref "R49")
      (value "470")
      (footprint "0805R")
      (description "Resistor")
      (fields (field (name "Comment") "RC0805JR-07470RL") (field (name "PUBLISHER") "Altium Limited"))
      (libsource (lib "") (part "Res2_2"))
    )
    (comp (ref "R50")
      (value "1K")
      (footprint "0805R")
      (description "Resistor")
      (fields (field (name "Comment") "RC0805JR-071KL") (field (name "PUBLISHER") "Altium Limited"))
      (libsource (lib "") (part "Res2_2"))
    )
    (comp (ref "R51")
      (value "1K")
      (footprint "0805R")
      (description "Resistor")
      (fields (field (name "Comment") "RC0805JR-071KL") (field (name "PUBLISHER") "Altium Limited"))
      (libsource (lib "") (part "Res2_2"))
    )
    (comp (ref "R52")
      (value "1K")
      (footprint "0805R")
      (description "Resistor")
      (fields (field (name "Comment") "RC0805JR-071KL") (field (name "PUBLISHER") "Altium Limited"))
      (libsource (lib "") (part "Res2_2"))
    )
    (comp (ref "R53")
      (value "470")
      (footprint "0805R")
      (description "Resistor")
      (fields (field (name "Comment") "RC0805JR-07470RL") (field (name "PUBLISHER") "Altium Limited"))
      (libsource (lib "") (part "Res2_2"))
    )
    (comp (ref "R54")
      (value "100R")
      (footprint "0805R")
      (description "Resistor")
      (fields (field (name "Comment") "RC0805JR-07100RL") (field (name "PUBLISHER") "Altium Limited"))
      (libsource (lib "") (part "Res2_2"))
    )
    (comp (ref "R55")
      (value "100K")
      (footprint "Potentiometer-3296W")
      (description "Potentiometer")
      (fields (field (name "Comment") "3296W-1-104") (field (name "PUBLISHER") "Altium Limited"))
      (libsource (lib "Miscellaneous Devices") (part "RPot"))
    )
    (comp (ref "R56")
      (value "100M")
      (footprint "0805R")
      (description "Resistor")
      (fields (field (name "Comment") "RC0805JR-07100ML") (field (name "PUBLISHER") "Altium Limited"))
      (libsource (lib "") (part "Res2_2"))
    )
    (comp (ref "R57")
      (value "2K")
      (footprint "0805R")
      (description "Resistor")
      (fields (field (name "Comment") "RC0805JR-072KL") (field (name "PUBLISHER") "Altium Limited"))
      (libsource (lib "") (part "Res2_2"))
    )
    (comp (ref "R58")
      (value "5.6K")
      (footprint "0805R")
      (description "Resistor")
      (fields (field (name "Comment") "RC0805JR-075600RL") (field (name "PUBLISHER") "Altium Limited"))
      (libsource (lib "") (part "Res2_2"))
    )
    (comp (ref "R59")
      (value "1M")
      (footprint "0805R")
      (description "Resistor")
      (fields (field (name "Comment") "RC0805JR-071000KL") (field (name "PUBLISHER") "Altium Limited"))
      (libsource (lib "") (part "Res2_1"))
    )
    (comp (ref "R60")
      (value "68K")
      (footprint "0805R")
      (description "Resistor")
      (fields (field (name "Comment") "RC0805JR-0768KL") (field (name "PUBLISHER") "Altium Limited"))
      (libsource (lib "") (part "Res2_1"))
    )
    (comp (ref "R61")
      (value "3296W-1-102")
      (footprint "Potentiometer-3296W")
      (description "Potentiometer")
      (fields (field (name "ALTIUM_VALUE") "1K") (field (name "PUBLISHER") "Altium Limited"))
      (libsource (lib "Miscellaneous Devices") (part "RPot"))
    )
    (comp (ref "R62")
      (value "RC0805JR-0768KL")
      (footprint "0805R")
      (description "Resistor")
      (fields (field (name "ALTIUM_VALUE") "68K") (field (name "PUBLISHER") "Altium Limited"))
      (libsource (lib "") (part "Res2_2"))
    )
    (comp (ref "R63")
      (value "2K")
      (footprint "0805R")
      (description "Resistor")
      (fields (field (name "Comment") "RC0805JR-072KL") (field (name "PUBLISHER") "Altium Limited"))
      (libsource (lib "") (part "Res2_2"))
    )
    (comp (ref "R64")
      (value "1K")
      (footprint "0805R")
      (description "Resistor")
      (fields (field (name "Comment") "RC0805JR-071KL") (field (name "PUBLISHER") "Altium Limited"))
      (libsource (lib "") (part "Res2_2"))
    )
    (comp (ref "R65")
      (value "1K")
      (footprint "0805R")
      (description "Resistor")
      (fields (field (name "Comment") "RC0805JR-071KL") (field (name "PUBLISHER") "Altium Limited"))
      (libsource (lib "") (part "Res2_2"))
    )
    (comp (ref "R66")
      (value "1K")
      (footprint "0805R")
      (description "Resistor")
      (fields (field (name "Comment") "RC0805JR-071KL") (field (name "PUBLISHER") "Altium Limited"))
      (libsource (lib "") (part "Res2_2"))
    )
    (comp (ref "R67")
      (value "10K")
      (footprint "0805R")
      (description "Resistor")
      (fields (field (name "Comment") "RC0805JR-0710KL") (field (name "PUBLISHER") "Altium Limited"))
      (libsource (lib "") (part "Res2_2"))
    )
    (comp (ref "R68")
      (value "RC0805JR-07470RL")
      (footprint "0805R")
      (description "Resistor")
      (fields (field (name "ALTIUM_VALUE") "470") (field (name "PUBLISHER") "Altium Limited"))
      (libsource (lib "Miscellaneous Devices") (part "Res2"))
    )
    (comp (ref "R69")
      (value "2K")
      (footprint "0805R")
      (description "Resistor")
      (fields (field (name "Comment") "RC0805JR-072KL") (field (name "PUBLISHER") "Altium Limited"))
      (libsource (lib "") (part "Res2_2"))
    )
    (comp (ref "R70")
      (value "2K")
      (footprint "0805R")
      (description "Resistor")
      (fields (field (name "Comment") "RC0805JR-072KL") (field (name "PUBLISHER") "Altium Limited"))
      (libsource (lib "") (part "Res2_2"))
    )
    (comp (ref "R71")
      (value "3.3K")
      (footprint "0805R")
      (description "Resistor")
      (fields (field (name "Comment") "RC0805JR-073300RL") (field (name "PUBLISHER") "Altium Limited"))
      (libsource (lib "") (part "Res2_2"))
    )
    (comp (ref "R72")
      (value "4.7K")
      (footprint "0805R")
      (description "Resistor")
      (fields (field (name "Comment") "RC0805JR-074700RL") (field (name "PUBLISHER") "Altium Limited"))
      (libsource (lib "") (part "Res2_2"))
    )
    (comp (ref "R73")
      (value "100M")
      (footprint "0805R")
      (description "Resistor")
      (fields (field (name "Comment") "RC0805JR-07100ML") (field (name "PUBLISHER") "Altium Limited"))
      (libsource (lib "Miscellaneous Devices") (part "Res2"))
    )
    (comp (ref "R74")
      (value "100K")
      (footprint "Potentiometer-3296W")
      (description "Potentiometer")
      (fields (field (name "Comment") "3296W-1-104") (field (name "PUBLISHER") "Altium Limited"))
      (libsource (lib "Miscellaneous Devices") (part "RPot"))
    )
    (comp (ref "U1")
      (value "WRB_ST(SD)-3WR2")
      (footprint "WRB_ST(SD)-3WR2")
      (libsource (lib "Standard-V0.0") (part "WRB_ST(SD)-3WR2"))
    )
    (comp (ref "U2") (value "VO2630") (footprint "so-8-n") (libsource (lib "Standard-V0.0") (part "VO2630")))
    (comp (ref "U3")
      (value "LM1117IMP-3.3/NOPB")
      (footprint "SOT223_N")
      (libsource (lib "Standard-V0.0") (part "LM1117IMP"))
    )
    (comp (ref "U4")
      (value "A05_S-1WR3")
      (footprint "A05_S-1WR3")
      (libsource (lib "Standard-V0.0") (part "A05_S-1WR3"))
    )
    (comp (ref "U5")
      (value "F0505XT-W2R3")
      (footprint "F0505XT-W2R3")
      (libsource (lib "Standard-V0.0") (part "F0505XT-W2R3"))
    )
    (comp (ref "U6")
      (value "STC12C5620AD")
      (footprint "SOP20")
      (libsource (lib "Standard-V0.0") (part "STC12C5620AD"))
    )
    (comp (ref "U7") (value "6N137") (footprint "so-8-n") (libsource (lib "") (part "6N137_1")))
    (comp (ref "U8") (value "6N137") (footprint "so-8-n") (libsource (lib "Standard-V0.0") (part "6N137")))
    (comp (ref "U9") (value "VO2630") (footprint "so-8-n") (libsource (lib "Standard-V0.0") (part "VO2630")))
    (comp (ref "U10") (value "VO2630") (footprint "so-8-n") (libsource (lib "Standard-V0.0") (part "VO2630")))
    (comp (ref "U11")
      (value "SN65LBC184")
      (footprint "so-8-n")
      (libsource (lib "TI_Sch_Lib") (part "SNx5LBC184"))
    )
    (comp (ref "U12") (value "DAC7611U") (footprint "so-8-n") (libsource (lib "TI_Sch_Lib") (part "DAC7611")))
    (comp (ref "U13") (value "TL431") (footprint "SOT-23-3") (libsource (lib "TI_Sch_Lib") (part "TL431")))
    (comp (ref "U14")
      (value "AD7124-8")
      (footprint "TI-RHB32-3150X3150TP_V")
      (libsource (lib "AD_Sch_Lib") (part "AD7124-8"))
    )
    (comp (ref "U15")
      (value "XTR111")
      (footprint "S-PDSO-G10")
      (libsource (lib "Standard-V0.0") (part "XTR111"))
    )
    (comp (ref "U16")
      (value "TL062ACD")
      (footprint "so-8-n")
      (fields (field (name "MANUFACTURER") "Texas Instruments"))
      (libsource (lib "TI Amplifiers and Linear Operational Amplifier General Purpose") (part "TL062ACD"))
    )
    (comp (ref "Y1")
      (value "XTAL")
      (footprint "11.0592MHz")
      (description "Crystal Oscillator")
      (fields (field (name "PUBLISHER") "Altium Limited"))
      (libsource (lib "Miscellaneous Devices") (part "XTAL"))
    )
  )
  (nets
    (net (code "1") (name "-15V") (class "Default")
      (node (ref "C19") (pin "1") (pinfunction "1_1") (pintype "passive"))
      (node (ref "C20") (pin "2") (pinfunction "2_2") (pintype "passive"))
      (node (ref "C61") (pin "1") (pinfunction "1_1") (pintype "passive"))
      (node (ref "C63") (pin "2") (pinfunction "2_2") (pintype "passive"))
      (node (ref "R55") (pin "1") (pinfunction "TOP_1") (pintype "passive"))
      (node (ref "R74") (pin "1") (pinfunction "TOP_1") (pintype "passive"))
      (node (ref "U16") (pin "4") (pinfunction "VCC-_4") (pintype "power_in"))
      (node (ref "U2") (pin "3") (pinfunction "CATHODE_2_3") (pintype "passive"))
      (node (ref "U4") (pin "4") (pinfunction "-VO_4") (pintype "passive"))
    )
    (net (code "2") (name "/5VON") (class "Default")
      (node (ref "R11") (pin "2") (pinfunction "2_2") (pintype "passive"))
      (node (ref "U2") (pin "7") (pinfunction "VO1_7") (pintype "passive"))
      (node (ref "U6") (pin "8") (pinfunction "ECI/T0/P3.4_8") (pintype "passive"))
    )
    (net (code "3") (name "/A1") (class "Default")
      (node (ref "R14") (pin "2") (pinfunction "2_2") (pintype "passive"))
      (node (ref "U6") (pin "15") (pinfunction "P1.3/ADC3_15") (pintype "passive"))
    )
    (net (code "4") (name "/A2") (class "Default")
      (node (ref "R15") (pin "2") (pinfunction "2_2") (pintype "passive"))
      (node (ref "U6") (pin "14") (pinfunction "P1.2/ADC2_14") (pintype "passive"))
    )
    (net (code "5") (name "/A3") (class "Default")
      (node (ref "R16") (pin "2") (pinfunction "2_2") (pintype "passive"))
      (node (ref "U6") (pin "13") (pinfunction "P1.1/ADC1/CLKOUT1_13") (pintype "passive"))
    )
    (net (code "6") (name "/A4") (class "Default")
      (node (ref "R17") (pin "2") (pinfunction "2_2") (pintype "passive"))
      (node (ref "U6") (pin "12") (pinfunction "P1.0/ADC0/CLKOUT0_12") (pintype "passive"))
    )
    (net (code "7") (name "/AIN8") (class "Default")
      (node (ref "R54") (pin "1") (pinfunction "1_1") (pintype "passive"))
      (node (ref "U14") (pin "14") (pinfunction "AIN8/IOUT/VBIAS_14") (pintype "passive"))
    )
    (net (code "8") (name "/AIN11") (class "Default")
      (node (ref "C58") (pin "1") (pinfunction "1_1") (pintype "passive"))
      (node (ref "R47") (pin "1") (pinfunction "1_1") (pintype "passive"))
      (node (ref "U14") (pin "17") (pinfunction "AIN11/IOUT/VBIAS_17") (pintype "passive"))
    )
    (net (code "9") (name "/CHN1_N") (class "Default")
      (node (ref "C44") (pin "2") (pinfunction "2_2") (pintype "passive"))
      (node (ref "C45") (pin "1") (pinfunction "1_1") (pintype "passive"))
      (node (ref "R30") (pin "1") (pinfunction "1_1") (pintype "passive"))
      (node (ref "U14") (pin "4") (pinfunction "AIN0/IOUT/VBIAS_4") (pintype "passive"))
    )
    (net (code "10") (name "/CHN1_P") (class "Default")
      (node (ref "C43") (pin "1") (pinfunction "1_1") (pintype "passive"))
      (node (ref "C44") (pin "1") (pinfunction "1_1") (pintype "passive"))
      (node (ref "R29") (pin "1") (pinfunction "1_1") (pintype "passive"))
      (node (ref "U14") (pin "5") (pinfunction "AIN1/IOUT/VBIAS_5") (pintype "passive"))
    )
    (net (code "11") (name "/CHN2_N") (class "Default")
      (node (ref "C41") (pin "2") (pinfunction "2_2") (pintype "passive"))
      (node (ref "C42") (pin "1") (pinfunction "1_1") (pintype "passive"))
      (node (ref "R28") (pin "1") (pinfunction "1_1") (pintype "passive"))
      (node (ref "U14") (pin "6") (pinfunction "AIN2/IOUT/VBIAS/P1_6") (pintype "passive"))
    )
    (net (code "12") (name "/CHN2_P") (class "Default")
      (node (ref "C40") (pin "1") (pinfunction "1_1") (pintype "passive"))
      (node (ref "C41") (pin "1") (pinfunction "1_1") (pintype "passive"))
      (node (ref "R27") (pin "1") (pinfunction "1_1") (pintype "passive"))
      (node (ref "U14") (pin "7") (pinfunction "AIN3/IOUT/VBIAS/P2_7") (pintype "passive"))
    )
    (net (code "13") (name "/CHN3_N") (class "Default")
      (node (ref "C38") (pin "2") (pinfunction "2_2") (pintype "passive"))
      (node (ref "C39") (pin "1") (pinfunction "1_1") (pintype "passive"))
      (node (ref "R26") (pin "1") (pinfunction "1_1") (pintype "passive"))
      (node (ref "U14") (pin "8") (pinfunction "AIN4/IOUT/VBIAS/P3_8") (pintype "passive"))
    )
    (net (code "14") (name "/CHN3_P") (class "Default")
      (node (ref "C37") (pin "1") (pinfunction "1_1") (pintype "passive"))
      (node (ref "C38") (pin "1") (pinfunction "1_1") (pintype "passive"))
      (node (ref "R25") (pin "1") (pinfunction "1_1") (pintype "passive"))
      (node (ref "U14") (pin "9") (pinfunction "AIN5/IOUT/VBIAS/P4_9") (pintype "passive"))
    )
    (net (code "15") (name "/CHN4_N") (class "Default")
      (node (ref "C35") (pin "2") (pinfunction "2_2") (pintype "passive"))
      (node (ref "C36") (pin "1") (pinfunction "1_1") (pintype "passive"))
      (node (ref "R24") (pin "1") (pinfunction "1_1") (pintype "passive"))
      (node (ref "U14") (pin "10") (pinfunction "AIN6/IOUT/VBIAS_10") (pintype "passive"))
    )
    (net (code "16") (name "/CHN4_P") (class "Default")
      (node (ref "C34") (pin "1") (pinfunction "1_1") (pintype "passive"))
      (node (ref "C35") (pin "1") (pinfunction "1_1") (pintype "passive"))
      (node (ref "R23") (pin "1") (pinfunction "1_1") (pintype "passive"))
      (node (ref "U14") (pin "11") (pinfunction "AIN7/IOUT/VBIAS_11") (pintype "passive"))
    )
    (net (code "17") (name "/CHN5_N") (class "Default")
      (node (ref "C56") (pin "2") (pinfunction "2_2") (pintype "passive"))
      (node (ref "C57") (pin "1") (pinfunction "1_1") (pintype "passive"))
      (node (ref "R46") (pin "1") (pinfunction "1_1") (pintype "passive"))
      (node (ref "U14") (pin "16") (pinfunction "AIN10/IOUT/VBIAS_16") (pintype "passive"))
    )
    (net (code "18") (name "/CHN5_P") (class "Default")
      (node (ref "C55") (pin "1") (pinfunction "1_1") (pintype "passive"))
      (node (ref "C56") (pin "1") (pinfunction "1_1") (pintype "passive"))
      (node (ref "R45") (pin "1") (pinfunction "1_1") (pintype "passive"))
      (node (ref "U14") (pin "15") (pinfunction "AIN9/IOUT/VBIAS_15") (pintype "passive"))
    )
    (net (code "19") (name "/CHN6_N") (class "Default")
      (node (ref "C70") (pin "2") (pinfunction "2_2") (pintype "passive"))
      (node (ref "C71") (pin "1") (pinfunction "1_1") (pintype "passive"))
      (node (ref "R59") (pin "2") (pinfunction "2_2") (pintype "passive"))
      (node (ref "R60") (pin "1") (pinfunction "1_1") (pintype "passive"))
      (node (ref "U14") (pin "19") (pinfunction "AIN13/IOUT/VBIAS_19") (pintype "passive"))
    )
    (net (code "20") (name "/CHN6_P") (class "Default")
      (node (ref "C69") (pin "1") (pinfunction "1_1") (pintype "passive"))
      (node (ref "C70") (pin "1") (pinfunction "1_1") (pintype "passive"))
      (node (ref "R64") (pin "1") (pinfunction "1_1") (pintype "passive"))
      (node (ref "U14") (pin "18") (pinfunction "AIN12/IOUT/VBIAS_18") (pintype "passive"))
    )
    (net (code "21") (name "/CHN7_N") (class "Default")
      (node (ref "C73") (pin "2") (pinfunction "2_2") (pintype "passive"))
      (node (ref "C74") (pin "1") (pinfunction "1_1") (pintype "passive"))
      (node (ref "R66") (pin "1") (pinfunction "1_1") (pintype "passive"))
      (node (ref "U14") (pin "21") (pinfunction "AIN15/IOUT/VBIAS/REFIN2-_21") (pintype "passive"))
    )
    (net (code "22") (name "/CHN7_P") (class "Default")
      (node (ref "C72") (pin "1") (pinfunction "1_1") (pintype "passive"))
      (node (ref "C73") (pin "1") (pinfunction "1_1") (pintype "passive"))
      (node (ref "R65") (pin "1") (pinfunction "1_1") (pintype "passive"))
      (node (ref "U14") (pin "20") (pinfunction "AIN14/IOUT/VBIAS/REFIN2+_20") (pintype "passive"))
    )
    (net (code "23") (name "/D1") (class "Default")
      (node (ref "R31") (pin "2") (pinfunction "2_2") (pintype "passive"))
      (node (ref "U12") (pin "2") (pinfunction "~{CS}_2") (pintype "passive"))
      (node (ref "U9") (pin "7") (pinfunction "VO1_7") (pintype "passive"))
    )
    (net (code "24") (name "/D2") (class "Default")
      (node (ref "R33") (pin "2") (pinfunction "2_2") (pintype "passive"))
      (node (ref "U12") (pin "3") (pinfunction "CLK_3") (pintype "passive"))
      (node (ref "U9") (pin "6") (pinfunction "VO2_6") (pintype "passive"))
    )
    (net (code "25") (name "/D3") (class "Default")
      (node (ref "R32") (pin "2") (pinfunction "2_2") (pintype "passive"))
      (node (ref "U10") (pin "7") (pinfunction "VO1_7") (pintype "passive"))
      (node (ref "U12") (pin "4") (pinfunction "SDI_4") (pintype "passive"))
    )
    (net (code "26") (name "/D4") (class "Default")
      (node (ref "R34") (pin "2") (pinfunction "2_2") (pintype "passive"))
      (node (ref "U10") (pin "6") (pinfunction "VO2_6") (pintype "passive"))
      (node (ref "U12") (pin "5") (pinfunction "~{LD}_5") (pintype "passive"))
    )
    (net (code "27") (name "/DIN") (class "Default")
      (node (ref "U14") (pin "29") (pinfunction "DIN_29") (pintype "passive"))
      (node (ref "U6") (pin "17") (pinfunction "P1.5/MOSI/ADC5_17") (pintype "passive"))
    )
    (net (code "28") (name "/DOUT") (class "Default")
      (node (ref "U14") (pin "28") (pinfunction "DOUT/~{RDY}_28") (pintype "passive"))
      (node (ref "U6") (pin "18") (pinfunction "P1.6/MISO/ADC6_18") (pintype "passive"))
    )
    (net (code "29") (name "/IS") (class "Default")
      (node (ref "Q2") (pin "3") (pinfunction "E_3") (pintype "passive"))
      (node (ref "R41") (pin "2") (pinfunction "2_2") (pintype "passive"))
      (node (ref "U15") (pin "2") (pinfunction "IS_2") (pintype "passive"))
    )
    (net (code "30") (name "/Iout") (class "Default")
      (node (ref "D19") (pin "2") (pinfunction "K_2") (pintype "passive"))
      (node (ref "P5") (pin "2") (pinfunction "2_2") (pintype "passive"))
      (node (ref "R40") (pin "1") (pinfunction "1_1") (pintype "passive"))
    )
    (net (code "31") (name "/PSW") (class "Default")
      (node (ref "R48") (pin "1") (pinfunction "1_1") (pintype "passive"))
      (node (ref "U14") (pin "25") (pinfunction "PSW_25") (pintype "passive"))
    )
    (net (code "32") (name "/PowerOK") (class "Default")
      (node (ref "Q1") (pin "2") (pinfunction "B_2") (pintype "passive"))
      (node (ref "U6") (pin "11") (pinfunction "P3.7/PCA0/PWM0_11") (pintype "passive"))
    )
    (net (code "33") (name "/REFIN1_N") (class "Default")
      (node (ref "C53") (pin "2") (pinfunction "2_2") (pintype "passive"))
      (node (ref "C54") (pin "1") (pinfunction "1_1") (pintype "passive"))
      (node (ref "R52") (pin "1") (pinfunction "1_1") (pintype "passive"))
      (node (ref "U14") (pin "13") (pinfunction "REFIN1-_13") (pintype "passive"))
    )
    (net (code "34") (name "/REFIN1_P") (class "Default")
      (node (ref "C52") (pin "1") (pinfunction "1_1") (pintype "passive"))
      (node (ref "C53") (pin "1") (pinfunction "1_1") (pintype "passive"))
      (node (ref "R51") (pin "1") (pinfunction "1_1") (pintype "passive"))
      (node (ref "U14") (pin "12") (pinfunction "REFIN1+_12") (pintype "passive"))
    )
    (net (code "35") (name "/REFOUT") (class "Default")
      (node (ref "NTC1") (pin "2") (pinfunction "2_2") (pintype "passive"))
      (node (ref "R59") (pin "1") (pinfunction "1_1") (pintype "passive"))
      (node (ref "R61") (pin "2") (pinfunction "BOT_2") (pintype "passive"))
      (node (ref "R65") (pin "2") (pinfunction "2_2") (pintype "passive"))
      (node (ref "U14") (pin "22") (pinfunction "REFOUT_22") (pintype "passive"))
    )
    (net (code "36") (name "/RS485_N") (class "Default")
      (node (ref "R19") (pin "2") (pinfunction "2_2") (pintype "passive"))
      (node (ref "U11") (pin "7") (pinfunction "B_7") (pintype "passive"))
    )
    (net (code "37") (name "/RS485_P") (class "Default")
      (node (ref "R18") (pin "1") (pinfunction "1_1") (pintype "passive"))
      (node (ref "U11") (pin "6") (pinfunction "A_6") (pintype "passive"))
    )
    (net (code "38") (name "/RxD") (class "Default")
      (node (ref "R12") (pin "1") (pinfunction "1_1") (pintype "passive"))
      (node (ref "U11") (pin "1") (pinfunction "R_1") (pintype "passive"))
      (node (ref "U8") (pin "2") (pinfunction "A_2") (pintype "passive"))
    )
    (net (code "39") (name "/SCLK") (class "Default")
      (node (ref "U14") (pin "30") (pinfunction "SCLK_30") (pintype "passive"))
      (node (ref "U6") (pin "19") (pinfunction "P1.7/SCLK/ADC7_19") (pintype "passive"))
    )
    (net (code "40") (name "/TxD") (class "Default")
      (node (ref "R10") (pin "1") (pinfunction "1_1") (pintype "passive"))
      (node (ref "U11") (pin "4") (pinfunction "D_4") (pintype "passive"))
      (node (ref "U7") (pin "6") (pinfunction "VO_6") (pintype "passive"))
    )
    (net (code "41") (name "/VG") (class "Default")
      (node (ref "Q2") (pin "1") (pinfunction "C_1") (pintype "passive"))
      (node (ref "Q3") (pin "1") (pinfunction "G_1") (pintype "passive"))
      (node (ref "U15") (pin "3") (pinfunction "VG_3") (pintype "passive"))
    )
    (net (code "42") (name "/VOUT") (class "Default")
      (node (ref "R57") (pin "2") (pinfunction "2_2") (pintype "passive"))
      (node (ref "R70") (pin "1") (pinfunction "1_1") (pintype "passive"))
      (node (ref "U12") (pin "8") (pinfunction "VOUT_8") (pintype "passive"))
    )
    (net (code "43") (name "/VREGS") (class "Default")
      (node (ref "R43") (pin "2") (pinfunction "2_2") (pintype "passive"))
      (node (ref "R44") (pin "1") (pinfunction "1_1") (pintype "passive"))
      (node (ref "U15") (pin "4") (pinfunction "REGS_4") (pintype "passive"))
    )
    (net (code "44") (name "/XTAL_N") (class "Default")
      (node (ref "C5") (pin "1") (pinfunction "1_1") (pintype "passive"))
      (node (ref "U6") (pin "5") (pinfunction "XTAL1_5") (pintype "passive"))
      (node (ref "Y1") (pin "1") (pinfunction "OSC1_1") (pintype "passive"))
    )
    (net (code "45") (name "/XTAL_P") (class "Default")
      (node (ref "C2") (pin "1") (pinfunction "1_1") (pintype "passive"))
      (node (ref "U6") (pin "4") (pinfunction "XTAL2_4") (pintype "passive"))
      (node (ref "Y1") (pin "2") (pinfunction "OSC2_2") (pintype "passive"))
    )
    (net (code "46") (name "/~{CS}") (class "Default")
      (node (ref "U14") (pin "32") (pinfunction "~{C}S_32") (pintype "passive"))
      (node (ref "U6") (pin "16") (pinfunction "P1.4/~{SS}/ADC4_16") (pintype "passive"))
    )
    (net (code "47") (name "/±15VON") (class "Default")
      (node (ref "R13") (pin "2") (pinfunction "2_2") (pintype "passive"))
      (node (ref "U2") (pin "6") (pinfunction "VO2_6") (pintype "passive"))
      (node (ref "U6") (pin "9") (pinfunction "PWM1/PCA1/T1/P3.5_9") (pintype "passive"))
    )
    (net (code "48") (name "3.3VCC") (class "Default")
      (node (ref "C1") (pin "1") (pinfunction "1_1") (pintype "passive"))
      (node (ref "C10") (pin "1") (pinfunction "1_1") (pintype "passive"))
      (node (ref "C14") (pin "1") (pinfunction "1_1") (pintype "passive"))
      (node (ref "C15") (pin "1") (pinfunction "1_1") (pintype "passive"))
      (node (ref "C26") (pin "1") (pinfunction "1_1") (pintype "passive"))
      (node (ref "C27") (pin "1") (pinfunction "1_1") (pintype "passive"))
      (node (ref "C3") (pin "1") (pinfunction "1_1") (pintype "passive"))
      (node (ref "C4") (pin "1") (pinfunction "1_1") (pintype "passive"))
      (node (ref "C64") (pin "1") (pinfunction "1_1") (pintype "passive"))
      (node (ref "C66") (pin "1") (pinfunction "1_1") (pintype "passive"))
      (node (ref "C67") (pin "1") (pinfunction "1_1") (pintype "passive"))
      (node (ref "C68") (pin "1") (pinfunction "1_1") (pintype "passive"))
      (node (ref "C9") (pin "1") (pinfunction "1_1") (pintype "passive"))
      (node (ref "R1") (pin "1") (pinfunction "1_1") (pintype "passive"))
      (node (ref "R11") (pin "1") (pinfunction "1_1") (pintype "passive"))
      (node (ref "R13") (pin "1") (pinfunction "1_1") (pintype "passive"))
      (node (ref "R53") (pin "1") (pinfunction "1_1") (pintype "passive"))
      (node (ref "R6") (pin "2") (pinfunction "2_2") (pintype "passive"))
      (node (ref "U14") (pin "2") (pinfunction "IOVDD_2") (pintype "passive"))
      (node (ref "U14") (pin "26") (pinfunction "AVDD_26") (pintype "passive"))
      (node (ref "U2") (pin "8") (pinfunction "VCC_8") (pintype "passive"))
      (node (ref "U3") (pin "3") (pinfunction "VOUT_3") (pintype "passive"))
      (node (ref "U6") (pin "20") (pinfunction "VCC_20") (pintype "passive"))
      (node (ref "U8") (pin "8") (pinfunction "VCC_8") (pintype "passive"))
    )
    (net (code "49") (name "5VDD") (class "Default")
      (node (ref "C16") (pin "1") (pinfunction "1_1") (pintype "passive"))
      (node (ref "C22") (pin "2") (pinfunction "2_2") (pintype "passive"))
      (node (ref "C23") (pin "1") (pinfunction "1_1") (pintype "passive"))
      (node (ref "C25") (pin "1") (pinfunction "1_1") (pintype "passive"))
      (node (ref "C28") (pin "1") (pinfunction "1_1") (pintype "passive"))
      (node (ref "C29") (pin "1") (pinfunction "1_1") (pintype "passive"))
      (node (ref "C30") (pin "1") (pinfunction "1_1") (pintype "passive"))
      (node (ref "C31") (pin "1") (pinfunction "1_1") (pintype "passive"))
      (node (ref "C32") (pin "1") (pinfunction "1_1") (pintype "passive"))
      (node (ref "C33") (pin "1") (pinfunction "1_1") (pintype "passive"))
      (node (ref "D4") (pin "2") (pinfunction "K_2") (pintype "passive"))
      (node (ref "R10") (pin "2") (pinfunction "2_2") (pintype "passive"))
      (node (ref "R12") (pin "2") (pinfunction "2_2") (pintype "passive"))
      (node (ref "R20") (pin "1") (pinfunction "1_1") (pintype "passive"))
      (node (ref "R3") (pin "2") (pinfunction "2_2") (pintype "passive"))
      (node (ref "R31") (pin "1") (pinfunction "1_1") (pintype "passive"))
      (node (ref "R32") (pin "1") (pinfunction "1_1") (pintype "passive"))
      (node (ref "R33") (pin "1") (pinfunction "1_1") (pintype "passive"))
      (node (ref "R34") (pin "1") (pinfunction "1_1") (pintype "passive"))
      (node (ref "U10") (pin "8") (pinfunction "VCC_8") (pintype "passive"))
      (node (ref "U11") (pin "2") (pinfunction "~{RE}_2") (pintype "passive"))
      (node (ref "U11") (pin "3") (pinfunction "DE_3") (pintype "passive"))
      (node (ref "U11") (pin "8") (pinfunction "VCC_8") (pintype "passive"))
      (node (ref "U5") (pin "5") (pinfunction "VO+_5") (pintype "passive"))
      (node (ref "U7") (pin "8") (pinfunction "VCC_8") (pintype "passive"))
      (node (ref "U9") (pin "8") (pinfunction "VCC_8") (pintype "passive"))
    )
    (net (code "50") (name "5VIN") (class "Default")
      (node (ref "C11") (pin "1") (pinfunction "1_1") (pintype "passive"))
      (node (ref "C12") (pin "2") (pinfunction "2_2") (pintype "passive"))
      (node (ref "C6") (pin "1") (pinfunction "1_1") (pintype "passive"))
      (node (ref "C7") (pin "1") (pinfunction "1_1") (pintype "passive"))
      (node (ref "C8") (pin "1") (pinfunction "1_1") (pintype "passive"))
      (node (ref "U1") (pin "5") (pinfunction "VO+_5") (pintype "passive"))
      (node (ref "U3") (pin "1") (pinfunction "VIN_1") (pintype "passive"))
      (node (ref "U4") (pin "1") (pinfunction "VIN+_1") (pintype "passive"))
      (node (ref "U5") (pin "2") (pinfunction "VIN+_2") (pintype "passive"))
    )
    (net (code "51") (name "5VIN-") (class "Default")
      (node (ref "C1") (pin "2") (pinfunction "2_2") (pintype "passive"))
      (node (ref "C10") (pin "2") (pinfunction "2_2") (pintype "passive"))
      (node (ref "C11") (pin "2") (pinfunction "2_2") (pintype "passive"))
      (node (ref "C12") (pin "1") (pinfunction "1_1") (pintype "passive"))
      (node (ref "C14") (pin "2") (pinfunction "2_2") (pintype "passive"))
      (node (ref "C15") (pin "2") (pinfunction "2_2") (pintype "passive"))
      (node (ref "C2") (pin "2") (pinfunction "2_2") (pintype "passive"))
      (node (ref "C26") (pin "2") (pinfunction "2_2") (pintype "passive"))
      (node (ref "C27") (pin "2") (pinfunction "2_2") (pintype "passive"))
      (node (ref "C3") (pin "2") (pinfunction "2_2") (pintype "passive"))
      (node (ref "C34") (pin "2") (pinfunction "2_2") (pintype "passive"))
      (node (ref "C36") (pin "2") (pinfunction "2_2") (pintype "passive"))
      (node (ref "C37") (pin "2") (pinfunction "2_2") (pintype "passive"))
      (node (ref "C39") (pin "2") (pinfunction "2_2") (pintype "passive"))
      (node (ref "C40") (pin "2") (pinfunction "2_2") (pintype "passive"))
      (node (ref "C42") (pin "2") (pinfunction "2_2") (pintype "passive"))
      (node (ref "C43") (pin "2") (pinfunction "2_2") (pintype "passive"))
      (node (ref "C45") (pin "2") (pinfunction "2_2") (pintype "passive"))
      (node (ref "C5") (pin "2") (pinfunction "2_2") (pintype "passive"))
      (node (ref "C51") (pin "2") (pinfunction "2_2") (pintype "passive"))
      (node (ref "C54") (pin "2") (pinfunction "2_2") (pintype "passive"))
      (node (ref "C55") (pin "2") (pinfunction "2_2") (pintype "passive"))
      (node (ref "C57") (pin "2") (pinfunction "2_2") (pintype "passive"))
      (node (ref "C58") (pin "2") (pinfunction "2_2") (pintype "passive"))
      (node (ref "C6") (pin "2") (pinfunction "2_2") (pintype "passive"))
      (node (ref "C62") (pin "1") (pinfunction "1_1") (pintype "passive"))
      (node (ref "C64") (pin "2") (pinfunction "2_2") (pintype "passive"))
      (node (ref "C66") (pin "2") (pinfunction "2_2") (pintype "passive"))
      (node (ref "C67") (pin "2") (pinfunction "2_2") (pintype "passive"))
      (node (ref "C68") (pin "2") (pinfunction "2_2") (pintype "passive"))
      (node (ref "C69") (pin "2") (pinfunction "2_2") (pintype "passive"))
      (node (ref "C7") (pin "2") (pinfunction "2_2") (pintype "passive"))
      (node (ref "C71") (pin "2") (pinfunction "2_2") (pintype "passive"))
      (node (ref "C72") (pin "2") (pinfunction "2_2") (pintype "passive"))
      (node (ref "C74") (pin "2") (pinfunction "2_2") (pintype "passive"))
      (node (ref "C76") (pin "1") (pinfunction "1_1") (pintype "passive"))
      (node (ref "C8") (pin "2") (pinfunction "2_2") (pintype "passive"))
      (node (ref "C9") (pin "2") (pinfunction "2_2") (pintype "passive"))
      (node (ref "D11") (pin "1") (pinfunction "ANODE_1") (pintype "passive"))
      (node (ref "D12") (pin "1") (pinfunction "ANODE_1") (pintype "passive"))
      (node (ref "D14") (pin "1") (pinfunction "ANODE_1") (pintype "passive"))
      (node (ref "D15") (pin "1") (pinfunction "ANODE_1") (pintype "passive"))
      (node (ref "D17") (pin "1") (pinfunction "ANODE_1") (pintype "passive"))
      (node (ref "D20") (pin "1") (pinfunction "ANODE_1") (pintype "passive"))
      (node (ref "D23") (pin "1") (pinfunction "ANODE_1") (pintype "passive"))
      (node (ref "D24") (pin "1") (pinfunction "ANODE_1") (pintype "passive"))
      (node (ref "D25") (pin "1") (pinfunction "ANODE_1") (pintype "passive"))
      (node (ref "D27") (pin "1") (pinfunction "ANODE_1") (pintype "passive"))
      (node (ref "D28") (pin "1") (pinfunction "ANODE_1") (pintype "passive"))
      (node (ref "D29") (pin "1") (pinfunction "ANODE_1") (pintype "passive"))
      (node (ref "D30") (pin "1") (pinfunction "ANODE_1") (pintype "passive"))
      (node (ref "D6") (pin "1") (pinfunction "ANODE_1") (pintype "passive"))
      (node (ref "D8") (pin "1") (pinfunction "ANODE_1") (pintype "passive"))
      (node (ref "D9") (pin "1") (pinfunction "ANODE_1") (pintype "passive"))
      (node (ref "P2") (pin "3") (pinfunction "3_3") (pintype "passive"))
      (node (ref "Q1") (pin "3") (pinfunction "E_3") (pintype "passive"))
      (node (ref "R2") (pin "1") (pinfunction "1_1") (pintype "passive"))
      (node (ref "R49") (pin "1") (pinfunction "1_1") (pintype "passive"))
      (node (ref "R58") (pin "1") (pinfunction "1_1") (pintype "passive"))
      (node (ref "R62") (pin "1") (pinfunction "1_1") (pintype "passive"))
      (node (ref "U1") (pin "7") (pinfunction "GND_7") (pintype "passive"))
      (node (ref "U10") (pin "2") (pinfunction "CATHODE_1_2") (pintype "passive"))
      (node (ref "U10") (pin "3") (pinfunction "CATHODE_2_3") (pintype "passive"))
      (node (ref "U14") (pin "23") (pinfunction "AVSS_23") (pintype "passive"))
      (node (ref "U14") (pin "3") (pinfunction "DGND_3") (pintype "passive"))
      (node (ref "U2") (pin "5") (pinfunction "GND_5") (pintype "passive"))
      (node (ref "U3") (pin "2") (pinfunction "ADJ_2") (pintype "passive"))
      (node (ref "U4") (pin "2") (pinfunction "VIN-_2") (pintype "passive"))
      (node (ref "U5") (pin "1") (pinfunction "VIN-_1") (pintype "passive"))
      (node (ref "U6") (pin "10") (pinfunction "GND_10") (pintype "passive"))
      (node (ref "U7") (pin "3") (pinfunction "C_3") (pintype "passive"))
      (node (ref "U8") (pin "5") (pinfunction "GND_5") (pintype "passive"))
      (node (ref "U9") (pin "2") (pinfunction "CATHODE_1_2") (pintype "passive"))
      (node (ref "U9") (pin "3") (pinfunction "CATHODE_2_3") (pintype "passive"))
    )
    (net (code "52") (name "15V") (class "Default")
      (node (ref "C17") (pin "1") (pinfunction "1_1") (pintype "passive"))
      (node (ref "C18") (pin "1") (pinfunction "1_1") (pintype "passive"))
      (node (ref "C49") (pin "1") (pinfunction "1_1") (pintype "passive"))
      (node (ref "C50") (pin "1") (pinfunction "1_1") (pintype "passive"))
      (node (ref "C59") (pin "2") (pinfunction "2_2") (pintype "passive"))
      (node (ref "C60") (pin "2") (pinfunction "2_2") (pintype "passive"))
      (node (ref "D22") (pin "2") (pinfunction "K_2") (pintype "passive"))
      (node (ref "R35") (pin "1") (pinfunction "1_1") (pintype "passive"))
      (node (ref "R4") (pin "2") (pinfunction "2_2") (pintype "passive"))
      (node (ref "R55") (pin "2") (pinfunction "BOT_2") (pintype "passive"))
      (node (ref "R68") (pin "1") (pinfunction "1_1") (pintype "passive"))
      (node (ref "R74") (pin "2") (pinfunction "BOT_2") (pintype "passive"))
      (node (ref "U15") (pin "1") (pinfunction "VSP_1") (pintype "passive"))
      (node (ref "U16") (pin "8") (pinfunction "VCC+_8") (pintype "power_in"))
      (node (ref "U4") (pin "6") (pinfunction "+VO_6") (pintype "passive"))
    )
    (net (code "53") (name "Net-(C51-Pad1)") (class "Default")
      (node (ref "C51") (pin "1") (pinfunction "1_1") (pintype "passive"))
      (node (ref "C52") (pin "2") (pinfunction "2_2") (pintype "passive"))
      (node (ref "R50") (pin "1") (pinfunction "1_1") (pintype "passive"))
      (node (ref "R54") (pin "2") (pinfunction "2_2") (pintype "passive"))
    )
    (net (code "54") (name "Net-(D1-A)") (class "Default")
      (node (ref "D1") (pin "1") (pinfunction "A_1") (pintype "passive"))
      (node (ref "R1") (pin "2") (pinfunction "2_2") (pintype "passive"))
    )
    (net (code "55") (name "Net-(D1-K)") (class "Default")
      (node (ref "D1") (pin "2") (pinfunction "K_2") (pintype "passive"))
      (node (ref "Q1") (pin "1") (pinfunction "C_1") (pintype "passive"))
    )
    (net (code "56") (name "Net-(D2-A)") (class "Default")
      (node (ref "D2") (pin "1") (pinfunction "A_1") (pintype "passive"))
      (node (ref "F1") (pin "2") (pinfunction "2_2") (pintype "passive"))
      (node (ref "R5") (pin "2") (pinfunction "2_2") (pintype "passive"))
    )
    (net (code "57") (name "Net-(D2-K)") (class "Default")
      (node (ref "D2") (pin "2") (pinfunction "K_2") (pintype "passive"))
      (node (ref "R8") (pin "2") (pinfunction "2_2") (pintype "passive"))
      (node (ref "R9") (pin "2") (pinfunction "2_2") (pintype "passive"))
    )
    (net (code "58") (name "Net-(D3-K)") (class "Default")
      (node (ref "C13") (pin "1") (pinfunction "1_1") (pintype "passive"))
      (node (ref "D3") (pin "2") (pinfunction "K_2") (pintype "passive"))
      (node (ref "L1") (pin "1") (pinfunction "1_1") (pintype "passive"))
      (node (ref "R8") (pin "1") (pinfunction "1_1") (pintype "passive"))
      (node (ref "R9") (pin "1") (pinfunction "1_1") (pintype "passive"))
    )
    (net (code "59") (name "Net-(D6-CATHODE)") (class "Default")
      (node (ref "D6") (pin "2") (pinfunction "CATHODE_2") (pintype "passive"))
      (node (ref "D7") (pin "2") (pinfunction "CATHODE_2") (pintype "passive"))
      (node (ref "P3") (pin "1") (pinfunction "1_1") (pintype "passive"))
      (node (ref "R23") (pin "2") (pinfunction "2_2") (pintype "passive"))
    )
    (net (code "60") (name "Net-(D7-ANODE)") (class "Default")
      (node (ref "D7") (pin "1") (pinfunction "ANODE_1") (pintype "passive"))
      (node (ref "D8") (pin "2") (pinfunction "CATHODE_2") (pintype "passive"))
      (node (ref "P3") (pin "2") (pinfunction "2_2") (pintype "passive"))
      (node (ref "R24") (pin "2") (pinfunction "2_2") (pintype "passive"))
    )
    (net (code "61") (name "Net-(D10-ANODE)") (class "Default")
      (node (ref "D10") (pin "1") (pinfunction "ANODE_1") (pintype "passive"))
      (node (ref "D11") (pin "2") (pinfunction "CATHODE_2") (pintype "passive"))
      (node (ref "P3") (pin "4") (pinfunction "4_4") (pintype "passive"))
      (node (ref "R26") (pin "2") (pinfunction "2_2") (pintype "passive"))
    )
    (net (code "62") (name "Net-(D10-CATHODE)") (class "Default")
      (node (ref "D10") (pin "2") (pinfunction "CATHODE_2") (pintype "passive"))
      (node (ref "D9") (pin "2") (pinfunction "CATHODE_2") (pintype "passive"))
      (node (ref "P3") (pin "3") (pinfunction "3_3") (pintype "passive"))
      (node (ref "R25") (pin "2") (pinfunction "2_2") (pintype "passive"))
    )
    (net (code "63") (name "Net-(D12-CATHODE)") (class "Default")
      (node (ref "D12") (pin "2") (pinfunction "CATHODE_2") (pintype "passive"))
      (node (ref "D13") (pin "2") (pinfunction "CATHODE_2") (pintype "passive"))
      (node (ref "P3") (pin "5") (pinfunction "5_5") (pintype "passive"))
      (node (ref "R27") (pin "2") (pinfunction "2_2") (pintype "passive"))
    )
    (net (code "64") (name "Net-(D13-ANODE)") (class "Default")
      (node (ref "D13") (pin "1") (pinfunction "ANODE_1") (pintype "passive"))
      (node (ref "D14") (pin "2") (pinfunction "CATHODE_2") (pintype "passive"))
      (node (ref "P3") (pin "6") (pinfunction "6_6") (pintype "passive"))
      (node (ref "R28") (pin "2") (pinfunction "2_2") (pintype "passive"))
    )
    (net (code "65") (name "Net-(D15-CATHODE)") (class "Default")
      (node (ref "D15") (pin "2") (pinfunction "CATHODE_2") (pintype "passive"))
      (node (ref "D16") (pin "2") (pinfunction "CATHODE_2") (pintype "passive"))
      (node (ref "P3") (pin "7") (pinfunction "7_7") (pintype "passive"))
      (node (ref "R29") (pin "2") (pinfunction "2_2") (pintype "passive"))
    )
    (net (code "66") (name "Net-(D16-ANODE)") (class "Default")
      (node (ref "D16") (pin "1") (pinfunction "ANODE_1") (pintype "passive"))
      (node (ref "D17") (pin "2") (pinfunction "CATHODE_2") (pintype "passive"))
      (node (ref "P3") (pin "8") (pinfunction "8_8") (pintype "passive"))
      (node (ref "R30") (pin "2") (pinfunction "2_2") (pintype "passive"))
    )
    (net (code "67") (name "Net-(D18-A)") (class "Default")
      (node (ref "D18") (pin "1") (pinfunction "A_1") (pintype "passive"))
      (node (ref "D5") (pin "2") (pinfunction "K_2") (pintype "passive"))
      (node (ref "P4") (pin "2") (pinfunction "2_2") (pintype "passive"))
      (node (ref "R19") (pin "1") (pinfunction "1_1") (pintype "passive"))
      (node (ref "R21") (pin "2") (pinfunction "2_2") (pintype "passive"))
      (node (ref "R22") (pin "1") (pinfunction "1_1") (pintype "passive"))
    )
    (net (code "68") (name "Net-(D18-K)") (class "Default")
      (node (ref "D18") (pin "2") (pinfunction "K_2") (pintype "passive"))
      (node (ref "D4") (pin "1") (pinfunction "A_1") (pintype "passive"))
      (node (ref "P4") (pin "1") (pinfunction "1_1") (pintype "passive"))
      (node (ref "R18") (pin "2") (pinfunction "2_2") (pintype "passive"))
      (node (ref "R20") (pin "2") (pinfunction "2_2") (pintype "passive"))
      (node (ref "R22") (pin "2") (pinfunction "2_2") (pintype "passive"))
    )
    (net (code "69") (name "Net-(D20-CATHODE)") (class "Default")
      (node (ref "D20") (pin "2") (pinfunction "CATHODE_2") (pintype "passive"))
      (node (ref "D21") (pin "2") (pinfunction "CATHODE_2") (pintype "passive"))
      (node (ref "P6") (pin "7") (pinfunction "7_7") (pintype "passive"))
      (node (ref "R42") (pin "2") (pinfunction "2_2") (pintype "passive"))
      (node (ref "R50") (pin "2") (pinfunction "2_2") (pintype "passive"))
      (node (ref "R51") (pin "2") (pinfunction "2_2") (pintype "passive"))
    )
    (net (code "70") (name "Net-(D21-ANODE)") (class "Default")
      (node (ref "D21") (pin "1") (pinfunction "ANODE_1") (pintype "passive"))
      (node (ref "D24") (pin "2") (pinfunction "CATHODE_2") (pintype "passive"))
      (node (ref "P6") (pin "6") (pinfunction "6_6") (pintype "passive"))
      (node (ref "R42") (pin "1") (pinfunction "1_1") (pintype "passive"))
      (node (ref "R52") (pin "2") (pinfunction "2_2") (pintype "passive"))
    )
    (net (code "71") (name "Net-(D22-A)") (class "Default")
      (node (ref "C48") (pin "1") (pinfunction "1_1") (pintype "passive"))
      (node (ref "D22") (pin "1") (pinfunction "A_1") (pintype "passive"))
      (node (ref "Q3") (pin "3") (pinfunction "S_3") (pintype "passive"))
      (node (ref "R40") (pin "2") (pinfunction "2_2") (pintype "passive"))
    )
    (net (code "72") (name "Net-(D23-CATHODE)") (class "Default")
      (node (ref "D23") (pin "2") (pinfunction "CATHODE_2") (pintype "passive"))
      (node (ref "P6") (pin "8") (pinfunction "8_8") (pintype "passive"))
      (node (ref "R53") (pin "2") (pinfunction "2_2") (pintype "passive"))
    )
    (net (code "73") (name "Net-(D25-CATHODE)") (class "Default")
      (node (ref "D25") (pin "2") (pinfunction "CATHODE_2") (pintype "passive"))
      (node (ref "D26") (pin "2") (pinfunction "CATHODE_2") (pintype "passive"))
      (node (ref "P6") (pin "5") (pinfunction "5_5") (pintype "passive"))
      (node (ref "R45") (pin "2") (pinfunction "2_2") (pintype "passive"))
    )
    (net (code "74") (name "Net-(D26-ANODE)") (class "Default")
      (node (ref "D26") (pin "1") (pinfunction "ANODE_1") (pintype "passive"))
      (node (ref "D27") (pin "2") (pinfunction "CATHODE_2") (pintype "passive"))
      (node (ref "P6") (pin "4") (pinfunction "4_4") (pintype "passive"))
      (node (ref "R46") (pin "2") (pinfunction "2_2") (pintype "passive"))
    )
    (net (code "75") (name "Net-(D28-CATHODE)") (class "Default")
      (node (ref "D28") (pin "2") (pinfunction "CATHODE_2") (pintype "passive"))
      (node (ref "P6") (pin "3") (pinfunction "3_3") (pintype "passive"))
      (node (ref "R47") (pin "2") (pinfunction "2_2") (pintype "passive"))
    )
    (net (code "76") (name "Net-(D29-CATHODE)") (class "Default")
      (node (ref "D29") (pin "2") (pinfunction "CATHODE_2") (pintype "passive"))
      (node (ref "P6") (pin "2") (pinfunction "2_2") (pintype "passive"))
      (node (ref "R48") (pin "2") (pinfunction "2_2") (pintype "passive"))
    )
    (net (code "77") (name "Net-(D30-CATHODE)") (class "Default")
      (node (ref "D30") (pin "2") (pinfunction "CATHODE_2") (pintype "passive"))
      (node (ref "P6") (pin "1") (pinfunction "1_1") (pintype "passive"))
      (node (ref "R49") (pin "2") (pinfunction "2_2") (pintype "passive"))
    )
    (net (code "78") (name "Net-(D31-K)") (class "Default")
      (node (ref "D31") (pin "2") (pinfunction "K_2") (pintype "passive"))
      (node (ref "P7") (pin "1") (pinfunction "1_1") (pintype "passive"))
      (node (ref "Q4") (pin "3") (pinfunction "E_3") (pintype "passive"))
      (node (ref "R63") (pin "1") (pinfunction "1_1") (pintype "passive"))
    )
    (net (code "79") (name "Net-(F1-Pad1)") (class "Default")
      (node (ref "F1") (pin "1") (pinfunction "1_1") (pintype "passive"))
      (node (ref "P1") (pin "4") (pinfunction "4_4") (pintype "passive"))
    )
    (net (code "80") (name "Net-(NTC1-Pad1)") (class "Default")
      (node (ref "NTC1") (pin "1") (pinfunction "1_1") (pintype "passive"))
      (node (ref "R58") (pin "2") (pinfunction "2_2") (pintype "passive"))
      (node (ref "R66") (pin "2") (pinfunction "2_2") (pintype "passive"))
    )
    (net (code "81") (name "Net-(Q2-B)") (class "Default")
      (node (ref "Q2") (pin "2") (pinfunction "B_2") (pintype "passive"))
      (node (ref "Q3") (pin "2") (pinfunction "D_2") (pintype "passive"))
      (node (ref "R41") (pin "1") (pinfunction "1_1") (pintype "passive"))
    )
    (net (code "82") (name "Net-(Q4-B)") (class "Default")
      (node (ref "Q4") (pin "2") (pinfunction "B_2") (pintype "passive"))
      (node (ref "R67") (pin "1") (pinfunction "1_1") (pintype "passive"))
    )
    (net (code "83") (name "Net-(Q4-C)") (class "Default")
      (node (ref "Q4") (pin "1") (pinfunction "C_1") (pintype "passive"))
      (node (ref "R68") (pin "2") (pinfunction "2_2") (pintype "passive"))
    )
    (net (code "84") (name "Net-(R55-TAP)") (class "Default")
      (node (ref "R55") (pin "3") (pinfunction "TAP_3") (pintype "passive"))
      (node (ref "R56") (pin "2") (pinfunction "2_2") (pintype "passive"))
    )
    (net (code "85") (name "Net-(R61-TAP)") (class "Default")
      (node (ref "R61") (pin "3") (pinfunction "TAP_3") (pintype "passive"))
      (node (ref "R64") (pin "2") (pinfunction "2_2") (pintype "passive"))
    )
    (net (code "86") (name "Net-(R61-TOP)") (class "Default")
      (node (ref "R60") (pin "2") (pinfunction "2_2") (pintype "passive"))
      (node (ref "R61") (pin "1") (pinfunction "TOP_1") (pintype "passive"))
      (node (ref "R62") (pin "2") (pinfunction "2_2") (pintype "passive"))
    )
    (net (code "87") (name "Net-(R71-Pad1)") (class "Default")
      (node (ref "R71") (pin "1") (pinfunction "1_1") (pintype "passive"))
      (node (ref "R72") (pin "2") (pinfunction "2_2") (pintype "passive"))
      (node (ref "R73") (pin "1") (pinfunction "1_1") (pintype "passive"))
    )
    (net (code "88") (name "Net-(R74-TAP)") (class "Default")
      (node (ref "R73") (pin "2") (pinfunction "2_2") (pintype "passive"))
      (node (ref "R74") (pin "3") (pinfunction "TAP_3") (pintype "passive"))
    )
    (net (code "89") (name "Net-(U2-ANODE_1)") (class "Default")
      (node (ref "R3") (pin "1") (pinfunction "1_1") (pintype "passive"))
      (node (ref "U2") (pin "1") (pinfunction "ANODE_1_1") (pintype "passive"))
    )
    (net (code "90") (name "Net-(U2-ANODE_2)") (class "Default")
      (node (ref "R4") (pin "1") (pinfunction "1_1") (pintype "passive"))
      (node (ref "U2") (pin "4") (pinfunction "ANODE_2_4") (pintype "passive"))
    )
    (net (code "91") (name "Net-(U6-RST)") (class "Default")
      (node (ref "C4") (pin "2") (pinfunction "2_2") (pintype "passive"))
      (node (ref "R2") (pin "2") (pinfunction "2_2") (pintype "passive"))
      (node (ref "U6") (pin "1") (pinfunction "RST_1") (pintype "passive"))
    )
    (net (code "92") (name "Net-(U6-RxD{slash}P3.0)") (class "Default")
      (node (ref "P2") (pin "2") (pinfunction "2_2") (pintype "passive"))
      (node (ref "R6") (pin "1") (pinfunction "1_1") (pintype "passive"))
      (node (ref "U6") (pin "2") (pinfunction "RxD/P3.0_2") (pintype "passive"))
      (node (ref "U8") (pin "6") (pinfunction "VO_6") (pintype "passive"))
    )
    (net (code "93") (name "Net-(U6-TxD{slash}P3.1)") (class "Default")
      (node (ref "P2") (pin "1") (pinfunction "1_1") (pintype "passive"))
      (node (ref "R7") (pin "1") (pinfunction "1_1") (pintype "passive"))
      (node (ref "U6") (pin "3") (pinfunction "TxD/P3.1_3") (pintype "passive"))
    )
    (net (code "94") (name "Net-(U7-A)") (class "Default")
      (node (ref "R7") (pin "2") (pinfunction "2_2") (pintype "passive"))
      (node (ref "U7") (pin "2") (pinfunction "A_2") (pintype "passive"))
    )
    (net (code "95") (name "Net-(U9-ANODE_1)") (class "Default")
      (node (ref "R14") (pin "1") (pinfunction "1_1") (pintype "passive"))
      (node (ref "U9") (pin "1") (pinfunction "ANODE_1_1") (pintype "passive"))
    )
    (net (code "96") (name "Net-(U9-ANODE_2)") (class "Default")
      (node (ref "R15") (pin "1") (pinfunction "1_1") (pintype "passive"))
      (node (ref "U9") (pin "4") (pinfunction "ANODE_2_4") (pintype "passive"))
    )
    (net (code "97") (name "Net-(U10-ANODE_1)") (class "Default")
      (node (ref "R16") (pin "1") (pinfunction "1_1") (pintype "passive"))
      (node (ref "U10") (pin "1") (pinfunction "ANODE_1_1") (pintype "passive"))
    )
    (net (code "98") (name "Net-(U10-ANODE_2)") (class "Default")
      (node (ref "R17") (pin "1") (pinfunction "1_1") (pintype "passive"))
      (node (ref "U10") (pin "4") (pinfunction "ANODE_2_4") (pintype "passive"))
    )
    (net (code "99") (name "Net-(U13-REF)") (class "Default")
      (node (ref "R36") (pin "1") (pinfunction "1_1") (pintype "passive"))
      (node (ref "R37") (pin "2") (pinfunction "2_2") (pintype "passive"))
      (node (ref "R38") (pin "1") (pinfunction "1_1") (pintype "passive"))
      (node (ref "U13") (pin "2") (pinfunction "REF_2") (pintype "passive"))
    )
    (net (code "100") (name "Net-(U14-REGCAPA)") (class "Default")
      (node (ref "C76") (pin "2") (pinfunction "2_2") (pintype "passive"))
      (node (ref "U14") (pin "24") (pinfunction "REGCAPA_24") (pintype "passive"))
    )
    (net (code "101") (name "Net-(U14-REGCAPD)") (class "Default")
      (node (ref "C62") (pin "2") (pinfunction "2_2") (pintype "passive"))
      (node (ref "U14") (pin "1") (pinfunction "REGCAPD_1") (pintype "passive"))
    )
    (net (code "102") (name "Net-(U15-SET)") (class "Default")
      (node (ref "R69") (pin "2") (pinfunction "2_2") (pintype "passive"))
      (node (ref "U15") (pin "7") (pinfunction "SET_7") (pintype "passive"))
    )
    (net (code "103") (name "Net-(U15-VIN)") (class "Default")
      (node (ref "C75") (pin "2") (pinfunction "2_2") (pintype "passive"))
      (node (ref "R70") (pin "2") (pinfunction "2_2") (pintype "passive"))
      (node (ref "R71") (pin "2") (pinfunction "2_2") (pintype "passive"))
      (node (ref "U15") (pin "6") (pinfunction "VIN_6") (pintype "passive"))
    )
    (net (code "104") (name "Net-(U16A-IN1+)") (class "Default")
      (node (ref "C65") (pin "1") (pinfunction "1_1") (pintype "passive"))
      (node (ref "R57") (pin "1") (pinfunction "1_1") (pintype "passive"))
      (node (ref "U16") (pin "3") (pinfunction "IN1+_3") (pintype "input"))
    )
    (net (code "105") (name "Net-(U16A-IN1-)") (class "Default")
      (node (ref "R56") (pin "1") (pinfunction "1_1") (pintype "passive"))
      (node (ref "R63") (pin "2") (pinfunction "2_2") (pintype "passive"))
      (node (ref "U16") (pin "2") (pinfunction "IN1-_2") (pintype "input"))
    )
    (net (code "106") (name "Net-(U16A-OUT1)") (class "Default")
      (node (ref "R67") (pin "2") (pinfunction "2_2") (pintype "passive"))
      (node (ref "U16") (pin "1") (pinfunction "OUT1_1") (pintype "output"))
    )
    (net (code "107") (name "SGND") (class "Default")
      (node (ref "C16") (pin "2") (pinfunction "2_2") (pintype "passive"))
      (node (ref "C22") (pin "1") (pinfunction "1_1") (pintype "passive"))
      (node (ref "C23") (pin "2") (pinfunction "2_2") (pintype "passive"))
      (node (ref "C25") (pin "2") (pinfunction "2_2") (pintype "passive"))
      (node (ref "C28") (pin "2") (pinfunction "2_2") (pintype "passive"))
      (node (ref "C29") (pin "2") (pinfunction "2_2") (pintype "passive"))
      (node (ref "C30") (pin "2") (pinfunction "2_2") (pintype "passive"))
      (node (ref "C31") (pin "2") (pinfunction "2_2") (pintype "passive"))
      (node (ref "C32") (pin "2") (pinfunction "2_2") (pintype "passive"))
      (node (ref "C33") (pin "2") (pinfunction "2_2") (pintype "passive"))
      (node (ref "D5") (pin "1") (pinfunction "A_1") (pintype "passive"))
      (node (ref "R21") (pin "1") (pinfunction "1_1") (pintype "passive"))
      (node (ref "R39") (pin "1") (pinfunction "1_1") (pintype "passive"))
      (node (ref "U10") (pin "5") (pinfunction "GND_5") (pintype "passive"))
      (node (ref "U11") (pin "5") (pinfunction "GND_5") (pintype "passive"))
      (node (ref "U2") (pin "2") (pinfunction "CATHODE_1_2") (pintype "passive"))
      (node (ref "U5") (pin "4") (pinfunction "GND_4") (pintype "passive"))
      (node (ref "U7") (pin "5") (pinfunction "GND_5") (pintype "passive"))
      (node (ref "U8") (pin "3") (pinfunction "C_3") (pintype "passive"))
      (node (ref "U9") (pin "5") (pinfunction "GND_5") (pintype "passive"))
    )
    (net (code "108") (name "VBIAS") (class "Default")
      (node (ref "R35") (pin "2") (pinfunction "2_2") (pintype "passive"))
      (node (ref "R37") (pin "1") (pinfunction "1_1") (pintype "passive"))
      (node (ref "R72") (pin "1") (pinfunction "1_1") (pintype "passive"))
      (node (ref "U13") (pin "1") (pinfunction "CATHODE_1") (pintype "passive"))
    )
    (net (code "109") (name "VIN+") (class "Default")
      (node (ref "C21") (pin "1") (pinfunction "1_1") (pintype "passive"))
      (node (ref "C24") (pin "1") (pinfunction "1_1") (pintype "passive"))
      (node (ref "L1") (pin "2") (pinfunction "2_2") (pintype "passive"))
      (node (ref "U1") (pin "4") (pinfunction "VIN+_4") (pintype "passive"))
    )
    (net (code "110") (name "VIN-") (class "Default")
      (node (ref "C13") (pin "2") (pinfunction "2_2") (pintype "passive"))
      (node (ref "C21") (pin "2") (pinfunction "2_2") (pintype "passive"))
      (node (ref "C24") (pin "2") (pinfunction "2_2") (pintype "passive"))
      (node (ref "D3") (pin "1") (pinfunction "A_1") (pintype "passive"))
      (node (ref "P1") (pin "1") (pinfunction "1_1") (pintype "passive"))
      (node (ref "R5") (pin "1") (pinfunction "1_1") (pintype "passive"))
      (node (ref "U1") (pin "1") (pinfunction "VIN-_1") (pintype "passive"))
    )
    (net (code "111") (name "VREGF") (class "Default")
      (node (ref "C46") (pin "1") (pinfunction "1_1") (pintype "passive"))
      (node (ref "C47") (pin "2") (pinfunction "2_2") (pintype "passive"))
      (node (ref "R43") (pin "1") (pinfunction "1_1") (pintype "passive"))
      (node (ref "U12") (pin "1") (pinfunction "VDD_1") (pintype "passive"))
      (node (ref "U12") (pin "6") (pinfunction "~{CLR}_6") (pintype "passive"))
      (node (ref "U15") (pin "5") (pinfunction "REGF_5") (pintype "passive"))
    )
    (net (code "112") (name "unconnected-(P1-Pad2)") (class "Default")
      (node (ref "P1") (pin "2") (pinfunction "2_2") (pintype "passive"))
    )
    (net (code "113") (name "unconnected-(P1-Pad3)") (class "Default")
      (node (ref "P1") (pin "3") (pinfunction "3_3") (pintype "passive"))
    )
    (net (code "114") (name "unconnected-(U1-NC-Pad6)") (class "Default")
      (node (ref "U1") (pin "6") (pinfunction "NC_6") (pintype "passive"))
    )
    (net (code "115") (name "unconnected-(U4-NC-Pad3)") (class "Default")
      (node (ref "U4") (pin "3") (pinfunction "NC_3") (pintype "passive"))
    )
    (net (code "116") (name "unconnected-(U5-NC-Pad8)") (class "Default")
      (node (ref "U5") (pin "8") (pinfunction "NC_8") (pintype "passive"))
    )
    (net (code "117") (name "unconnected-(U6-~{INT0}{slash}P3.2-Pad6)") (class "Default")
      (node (ref "U6") (pin "6") (pinfunction "~{INT0}/P3.2_6") (pintype "passive"))
    )
    (net (code "118") (name "unconnected-(U6-~{INT1}{slash}P3.3-Pad7)") (class "Default")
      (node (ref "U6") (pin "7") (pinfunction "~{INT1}/P3.3_7") (pintype "passive"))
    )
    (net (code "119") (name "unconnected-(U7-NC-Pad1)") (class "Default")
      (node (ref "U7") (pin "1") (pinfunction "NC_1") (pintype "passive"))
    )
    (net (code "120") (name "unconnected-(U7-NC-Pad4)") (class "Default")
      (node (ref "U7") (pin "4") (pinfunction "NC_4") (pintype "passive"))
    )
    (net (code "121") (name "unconnected-(U7-VE-Pad7)") (class "Default")
      (node (ref "U7") (pin "7") (pinfunction "VE_7") (pintype "passive"))
    )
    (net (code "122") (name "unconnected-(U8-NC-Pad1)") (class "Default")
      (node (ref "U8") (pin "1") (pinfunction "NC_1") (pintype "passive"))
    )
    (net (code "123") (name "unconnected-(U8-NC-Pad4)") (class "Default")
      (node (ref "U8") (pin "4") (pinfunction "NC_4") (pintype "passive"))
    )
    (net (code "124") (name "unconnected-(U8-VE-Pad7)") (class "Default")
      (node (ref "U8") (pin "7") (pinfunction "VE_7") (pintype "passive"))
    )
    (net (code "125") (name "unconnected-(U14-CLK-Pad31)") (class "Default")
      (node (ref "U14") (pin "31") (pinfunction "CLK_31") (pintype "passive"))
    )
    (net (code "126") (name "unconnected-(U14-~{SYNC}-Pad27)") (class "Default")
      (node (ref "U14") (pin "27") (pinfunction "~{SYNC}_27") (pintype "passive"))
    )
    (net (code "127") (name "unconnected-(U15-~{EF}-Pad8)") (class "Default")
      (node (ref "U15") (pin "8") (pinfunction "~{EF}_8") (pintype "passive"))
    )
    (net (code "128") (name "±15VGND") (class "Default")
      (node (ref "C17") (pin "2") (pinfunction "2_2") (pintype "passive"))
      (node (ref "C18") (pin "2") (pinfunction "2_2") (pintype "passive"))
      (node (ref "C19") (pin "2") (pinfunction "2_2") (pintype "passive"))
      (node (ref "C20") (pin "1") (pinfunction "1_1") (pintype "passive"))
      (node (ref "C46") (pin "2") (pinfunction "2_2") (pintype "passive"))
      (node (ref "C47") (pin "1") (pinfunction "1_1") (pintype "passive"))
      (node (ref "C48") (pin "2") (pinfunction "2_2") (pintype "passive"))
      (node (ref "C49") (pin "2") (pinfunction "2_2") (pintype "passive"))
      (node (ref "C50") (pin "2") (pinfunction "2_2") (pintype "passive"))
      (node (ref "C59") (pin "1") (pinfunction "1_1") (pintype "passive"))
      (node (ref "C60") (pin "1") (pinfunction "1_1") (pintype "passive"))
      (node (ref "C61") (pin "2") (pinfunction "2_2") (pintype "passive"))
      (node (ref "C63") (pin "1") (pinfunction "1_1") (pintype "passive"))
      (node (ref "C65") (pin "2") (pinfunction "2_2") (pintype "passive"))
      (node (ref "C75") (pin "1") (pinfunction "1_1") (pintype "passive"))
      (node (ref "D19") (pin "1") (pinfunction "A_1") (pintype "passive"))
      (node (ref "D31") (pin "1") (pinfunction "A_1") (pintype "passive"))
      (node (ref "P5") (pin "1") (pinfunction "1_1") (pintype "passive"))
      (node (ref "P7") (pin "2") (pinfunction "2_2") (pintype "passive"))
      (node (ref "R36") (pin "2") (pinfunction "2_2") (pintype "passive"))
      (node (ref "R38") (pin "2") (pinfunction "2_2") (pintype "passive"))
      (node (ref "R39") (pin "2") (pinfunction "2_2") (pintype "passive"))
      (node (ref "R44") (pin "2") (pinfunction "2_2") (pintype "passive"))
      (node (ref "R69") (pin "1") (pinfunction "1_1") (pintype "passive"))
      (node (ref "U12") (pin "7") (pinfunction "GND_7") (pintype "passive"))
      (node (ref "U13") (pin "3") (pinfunction "ANODE_3") (pintype "passive"))
      (node (ref "U15") (pin "10") (pinfunction "GND_10") (pintype "passive"))
      (node (ref "U15") (pin "9") (pinfunction "OD_9") (pintype "passive"))
      (node (ref "U4") (pin "5") (pinfunction "GND_5") (pintype "passive"))
    )
  )
)
